# IndAlarmIf2.net
KiCad netlist of a schematic drawn in Altium Designer
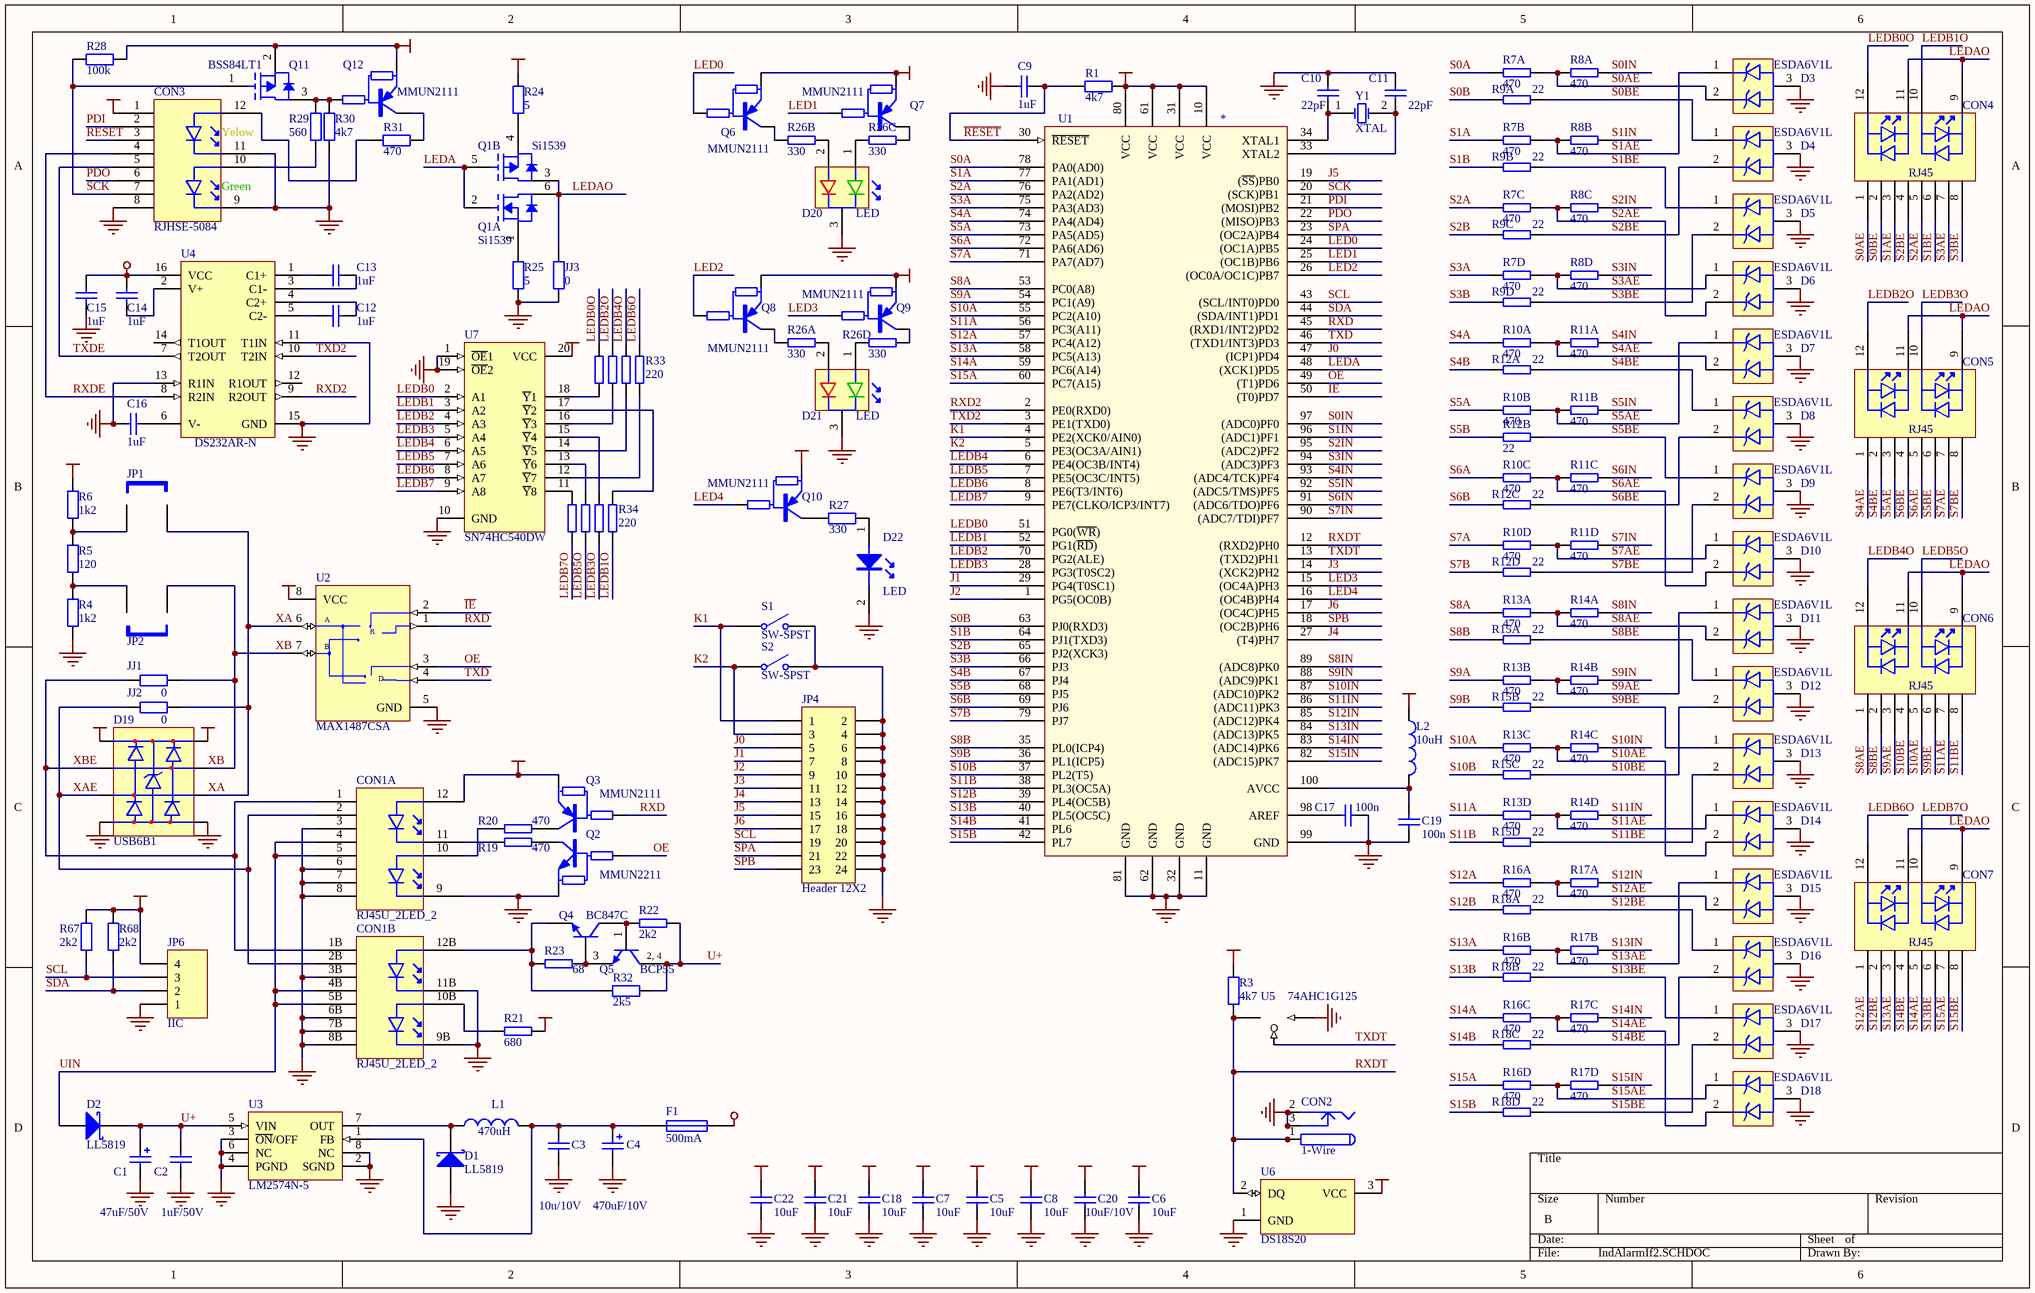
[diagram p0: IndAlarmIf2.SCHDOC]

(export (version "E")
  (design (tool "Eeschema 10.0.6"))
  (components
    (comp (ref "C1")
      (value "47uF/50V")
      (footprint "C8X11RM3.5")
      (description "Polarized Capacitor (Radial)")
      (fields (field (name "Comment") "Cap Pol1") (field (name "PUBLISHER") "Altium Limited"))
      (libsource (lib "Miscellaneous Devices") (part "Cap Pol1"))
    )
    (comp (ref "C2")
      (value "1uF/50V")
      (footprint "CC3225-1210")
      (description "Capacitor (Semiconductor SIM Model)")
      (fields (field (name "Comment") "Cap Semi") (field (name "PUBLISHER") "Altium Limited"))
      (libsource (lib "Miscellaneous Devices") (part "Cap Semi"))
    )
    (comp (ref "C3")
      (value "10u/10V")
      (footprint "CC3225-1210")
      (description "Capacitor (Semiconductor SIM Model)")
      (fields (field (name "Comment") "Cap Semi") (field (name "PUBLISHER") "Altium Limited"))
      (libsource (lib "Miscellaneous Devices") (part "Cap Semi"))
    )
    (comp (ref "C4")
      (value "470uF/10V")
      (footprint "C8X11RM3.5")
      (description "Polarized Capacitor (Radial)")
      (fields (field (name "Comment") "Cap Pol1") (field (name "PUBLISHER") "Altium Limited"))
      (libsource (lib "Miscellaneous Devices") (part "Cap Pol1"))
    )
    (comp (ref "C5")
      (value "10uF")
      (footprint "CC3216-1206")
      (description "Capacitor (Semiconductor SIM Model)")
      (fields (field (name "Comment") "Cap Semi") (field (name "PUBLISHER") "Altium Limited"))
      (libsource (lib "Miscellaneous Devices") (part "Cap Semi"))
    )
    (comp (ref "C6")
      (value "10uF")
      (footprint "CC3216-1206")
      (description "Capacitor (Semiconductor SIM Model)")
      (fields (field (name "Comment") "Cap Semi") (field (name "PUBLISHER") "Altium Limited"))
      (libsource (lib "Miscellaneous Devices") (part "Cap Semi"))
    )
    (comp (ref "C7")
      (value "10uF")
      (footprint "CC3216-1206")
      (description "Capacitor (Semiconductor SIM Model)")
      (fields (field (name "Comment") "Cap Semi") (field (name "PUBLISHER") "Altium Limited"))
      (libsource (lib "Miscellaneous Devices") (part "Cap Semi"))
    )
    (comp (ref "C8")
      (value "10uF")
      (footprint "CC3225-1210")
      (description "Capacitor (Semiconductor SIM Model)")
      (fields (field (name "Comment") "Cap Semi") (field (name "PUBLISHER") "Altium Limited"))
      (libsource (lib "Miscellaneous Devices") (part "Cap Semi"))
    )
    (comp (ref "C9")
      (value "1uF")
      (footprint "CC2012-0805")
      (description "Capacitor (Semiconductor SIM Model)")
      (fields (field (name "Comment") "Cap Semi") (field (name "PUBLISHER") "Altium Limited"))
      (libsource (lib "Miscellaneous Devices") (part "Cap Semi"))
    )
    (comp (ref "C10")
      (value "22pF")
      (footprint "CC2012-0805")
      (description "Capacitor (Semiconductor SIM Model)")
      (fields (field (name "Comment") "Cap Semi") (field (name "PUBLISHER") "Altium Limited"))
      (libsource (lib "Miscellaneous Devices") (part "Cap Semi"))
    )
    (comp (ref "C11")
      (value "22pF")
      (footprint "CC2012-0805")
      (description "Capacitor (Semiconductor SIM Model)")
      (fields (field (name "Comment") "Cap Semi") (field (name "PUBLISHER") "Altium Limited"))
      (libsource (lib "Miscellaneous Devices") (part "Cap Semi"))
    )
    (comp (ref "C12")
      (value "1uF")
      (footprint "CC2012-0805")
      (description "Capacitor (Semiconductor SIM Model)")
      (fields (field (name "Comment") "Cap Semi") (field (name "PUBLISHER") "Altium Limited"))
      (libsource (lib "Miscellaneous Devices") (part "Cap Semi"))
    )
    (comp (ref "C13")
      (value "1uF")
      (footprint "CC2012-0805")
      (description "Capacitor (Semiconductor SIM Model)")
      (fields (field (name "Comment") "Cap Semi") (field (name "PUBLISHER") "Altium Limited"))
      (libsource (lib "Miscellaneous Devices") (part "Cap Semi"))
    )
    (comp (ref "C14")
      (value "1uF")
      (footprint "CC2012-0805")
      (description "Capacitor (Semiconductor SIM Model)")
      (fields (field (name "Comment") "Cap Semi") (field (name "PUBLISHER") "Altium Limited"))
      (libsource (lib "Miscellaneous Devices") (part "Cap Semi"))
    )
    (comp (ref "C15")
      (value "1uF")
      (footprint "CC3216-1206")
      (description "Capacitor (Semiconductor SIM Model)")
      (fields (field (name "Comment") "Cap Semi") (field (name "PUBLISHER") "Altium Limited"))
      (libsource (lib "Miscellaneous Devices") (part "Cap Semi"))
    )
    (comp (ref "C16")
      (value "1uF")
      (footprint "CC2012-0805")
      (description "Capacitor (Semiconductor SIM Model)")
      (fields (field (name "Comment") "Cap Semi") (field (name "PUBLISHER") "Altium Limited"))
      (libsource (lib "Miscellaneous Devices") (part "Cap Semi"))
    )
    (comp (ref "C17")
      (value "100n")
      (footprint "CC2012-0805")
      (description "Capacitor (Semiconductor SIM Model)")
      (fields (field (name "Comment") "Cap Semi") (field (name "PUBLISHER") "Altium Limited"))
      (libsource (lib "Miscellaneous Devices") (part "Cap Semi"))
    )
    (comp (ref "C18")
      (value "10uF")
      (footprint "CC3216-1206")
      (description "Capacitor (Semiconductor SIM Model)")
      (fields (field (name "Comment") "Cap Semi") (field (name "PUBLISHER") "Altium Limited"))
      (libsource (lib "Miscellaneous Devices") (part "Cap Semi"))
    )
    (comp (ref "C19")
      (value "100n")
      (footprint "CC3216-1206")
      (description "Capacitor (Semiconductor SIM Model)")
      (fields (field (name "Comment") "Cap Semi") (field (name "PUBLISHER") "Altium Limited"))
      (libsource (lib "Miscellaneous Devices") (part "Cap Semi"))
    )
    (comp (ref "C20")
      (value "10uF/10V")
      (footprint "CC3216-1206")
      (description "Capacitor (Semiconductor SIM Model)")
      (fields (field (name "Comment") "Cap Semi") (field (name "PUBLISHER") "Altium Limited"))
      (libsource (lib "Miscellaneous Devices") (part "Cap Semi"))
    )
    (comp (ref "C21")
      (value "10uF")
      (footprint "CC3216-1206")
      (description "Capacitor (Semiconductor SIM Model)")
      (fields (field (name "Comment") "Cap Semi") (field (name "PUBLISHER") "Altium Limited"))
      (libsource (lib "Miscellaneous Devices") (part "Cap Semi"))
    )
    (comp (ref "C22")
      (value "10uF")
      (footprint "CC3216-1206")
      (description "Capacitor (Semiconductor SIM Model)")
      (fields (field (name "Comment") "Cap Semi") (field (name "PUBLISHER") "Altium Limited"))
      (libsource (lib "Miscellaneous Devices") (part "Cap Semi"))
    )
    (comp (ref "CON1")
      (value "RJ45U_2LED_2")
      (footprint "RJHS-508x-2")
      (libsource (lib "mySCHLIB") (part "RJ45U_2LED_2"))
    )
    (comp (ref "CON2")
      (value "1-Wire")
      (footprint "KLD-0202")
      (description "Low Voltage Power Supply Connector")
      (fields (field (name "PUBLISHER") "Altium Limited"))
      (libsource (lib "Miscellaneous Connectors") (part "PWR2.5"))
    )
    (comp (ref "CON3")
      (value "RJHSE-5084")
      (footprint "RJHS-508x")
      (libsource (lib "mySCHLIB") (part "RJ45U_2LED"))
    )
    (comp (ref "CON4")
      (value "RJ45")
      (footprint "RJHS-508x")
      (libsource (lib "mySCHLIB") (part "RJ45U_2LED_BI"))
    )
    (comp (ref "CON5")
      (value "RJ45")
      (footprint "RJHS-508x")
      (libsource (lib "mySCHLIB") (part "RJ45U_2LED_BI"))
    )
    (comp (ref "CON6")
      (value "RJ45")
      (footprint "RJHS-508x")
      (libsource (lib "mySCHLIB") (part "RJ45U_2LED_BI"))
    )
    (comp (ref "CON7")
      (value "RJ45")
      (footprint "RJHS-508x")
      (libsource (lib "mySCHLIB") (part "RJ45U_2LED_BI"))
    )
    (comp (ref "D1")
      (value "LL5819")
      (footprint "MELF")
      (description "Schottky Diode")
      (fields (field (name "PUBLISHER") "Altium Limited"))
      (libsource (lib "Miscellaneous Devices") (part "D Schottky"))
    )
    (comp (ref "D2")
      (value "LL5819")
      (footprint "MELF")
      (description "Schottky Diode")
      (fields (field (name "PUBLISHER") "Altium Limited"))
      (libsource (lib "Miscellaneous Devices") (part "D Schottky"))
    )
    (comp (ref "D3")
      (value "ESDA6V1L")
      (footprint "SO-G3/C2.5")
      (description "DUAL TRANSIL ARRAY\r\nFOR ESD PROTECTION")
      (libsource (lib "mySCHLIB") (part "ESDA6V1L"))
    )
    (comp (ref "D4")
      (value "ESDA6V1L")
      (footprint "SO-G3/C2.5")
      (description "DUAL TRANSIL ARRAY\r\nFOR ESD PROTECTION")
      (libsource (lib "mySCHLIB") (part "ESDA6V1L"))
    )
    (comp (ref "D5")
      (value "ESDA6V1L")
      (footprint "SO-G3/C2.5")
      (description "DUAL TRANSIL ARRAY\r\nFOR ESD PROTECTION")
      (libsource (lib "mySCHLIB") (part "ESDA6V1L"))
    )
    (comp (ref "D6")
      (value "ESDA6V1L")
      (footprint "SO-G3/C2.5")
      (description "DUAL TRANSIL ARRAY\r\nFOR ESD PROTECTION")
      (libsource (lib "mySCHLIB") (part "ESDA6V1L"))
    )
    (comp (ref "D7")
      (value "ESDA6V1L")
      (footprint "SO-G3/C2.5")
      (description "DUAL TRANSIL ARRAY\r\nFOR ESD PROTECTION")
      (libsource (lib "mySCHLIB") (part "ESDA6V1L"))
    )
    (comp (ref "D8")
      (value "ESDA6V1L")
      (footprint "SO-G3/C2.5")
      (description "DUAL TRANSIL ARRAY\r\nFOR ESD PROTECTION")
      (libsource (lib "mySCHLIB") (part "ESDA6V1L"))
    )
    (comp (ref "D9")
      (value "ESDA6V1L")
      (footprint "SO-G3/C2.5")
      (description "DUAL TRANSIL ARRAY\r\nFOR ESD PROTECTION")
      (libsource (lib "mySCHLIB") (part "ESDA6V1L"))
    )
    (comp (ref "D10")
      (value "ESDA6V1L")
      (footprint "SO-G3/C2.5")
      (description "DUAL TRANSIL ARRAY\r\nFOR ESD PROTECTION")
      (libsource (lib "mySCHLIB") (part "ESDA6V1L"))
    )
    (comp (ref "D11")
      (value "ESDA6V1L")
      (footprint "SO-G3/C2.5")
      (description "DUAL TRANSIL ARRAY\r\nFOR ESD PROTECTION")
      (libsource (lib "mySCHLIB") (part "ESDA6V1L"))
    )
    (comp (ref "D12")
      (value "ESDA6V1L")
      (footprint "SO-G3/C2.5")
      (description "DUAL TRANSIL ARRAY\r\nFOR ESD PROTECTION")
      (libsource (lib "mySCHLIB") (part "ESDA6V1L"))
    )
    (comp (ref "D13")
      (value "ESDA6V1L")
      (footprint "SO-G3/C2.5")
      (description "DUAL TRANSIL ARRAY\r\nFOR ESD PROTECTION")
      (libsource (lib "mySCHLIB") (part "ESDA6V1L"))
    )
    (comp (ref "D14")
      (value "ESDA6V1L")
      (footprint "SO-G3/C2.5")
      (description "DUAL TRANSIL ARRAY\r\nFOR ESD PROTECTION")
      (libsource (lib "mySCHLIB") (part "ESDA6V1L"))
    )
    (comp (ref "D15")
      (value "ESDA6V1L")
      (footprint "SO-G3/C2.5")
      (description "DUAL TRANSIL ARRAY\r\nFOR ESD PROTECTION")
      (libsource (lib "mySCHLIB") (part "ESDA6V1L"))
    )
    (comp (ref "D16")
      (value "ESDA6V1L")
      (footprint "SO-G3/C2.5")
      (description "DUAL TRANSIL ARRAY\r\nFOR ESD PROTECTION")
      (libsource (lib "mySCHLIB") (part "ESDA6V1L"))
    )
    (comp (ref "D17")
      (value "ESDA6V1L")
      (footprint "SO-G3/C2.5")
      (description "DUAL TRANSIL ARRAY\r\nFOR ESD PROTECTION")
      (libsource (lib "mySCHLIB") (part "ESDA6V1L"))
    )
    (comp (ref "D18")
      (value "ESDA6V1L")
      (footprint "SO-G3/C2.5")
      (description "DUAL TRANSIL ARRAY\r\nFOR ESD PROTECTION")
      (libsource (lib "mySCHLIB") (part "ESDA6V1L"))
    )
    (comp (ref "D19") (value "USB6B1") (footprint "NSO8") (libsource (lib "mySCHLIB") (part "USB6B1")))
    (comp (ref "D20") (value "LED") (footprint "LED3mm - 2") (libsource (lib "mySCHLIB") (part "2LED_A")))
    (comp (ref "D21") (value "LED") (footprint "LED3mm - 2") (libsource (lib "mySCHLIB") (part "2LED_A")))
    (comp (ref "D22") (value "LED") (footprint "myLIB:LED3mm") (libsource (lib "mySCHLIB") (part "LED12")))
    (comp (ref "F1")
      (value "500mA")
      (footprint "minifuse")
      (description "Fuse")
      (fields (field (name "PUBLISHER") "Altium Limited"))
      (libsource (lib "Miscellaneous Devices") (part "Fuse 1"))
    )
    (comp (ref "JJ1")
      (value "0")
      (footprint "CR2012-0805")
      (description "Semiconductor Resistor")
      (fields (field (name "PUBLISHER") "Altium Limited"))
      (libsource (lib "") (part "Res Semi_1"))
    )
    (comp (ref "JJ2")
      (value "0")
      (footprint "CR2012-0805")
      (description "Semiconductor Resistor")
      (fields (field (name "PUBLISHER") "Altium Limited"))
      (libsource (lib "") (part "Res Semi_1"))
    )
    (comp (ref "JJ3")
      (value "0")
      (footprint "CR2012-0805")
      (description "Semiconductor Resistor")
      (fields (field (name "PUBLISHER") "Altium Limited"))
      (libsource (lib "Miscellaneous Devices") (part "Res Semi"))
    )
    (comp (ref "JP1")
      (value "Jumper")
      (footprint "JP")
      (description "Jumper Wire")
      (fields (field (name "PUBLISHER") "Altium Limited"))
      (libsource (lib "Miscellaneous Devices") (part "Jumper"))
    )
    (comp (ref "JP2")
      (value "Jumper")
      (footprint "JP")
      (description "Jumper Wire")
      (fields (field (name "PUBLISHER") "Altium Limited"))
      (libsource (lib "Miscellaneous Devices") (part "Jumper"))
    )
    (comp (ref "JP4")
      (value "Header 12X2")
      (footprint "HDR2X12")
      (description "Header, 12-Pin, Dual row")
      (fields (field (name "PUBLISHER") "Altium Limited"))
      (libsource (lib "Miscellaneous Connectors") (part "Header 12X2"))
    )
    (comp (ref "JP6")
      (value "IIC")
      (footprint "HDR1X4")
      (description "Header, 4-Pin")
      (fields (field (name "PUBLISHER") "Altium Limited"))
      (libsource (lib "Miscellaneous Connectors") (part "Header 4"))
    )
    (comp (ref "L1")
      (value "470uH")
      (footprint "SSL1306T - NPI27H")
      (description "Inductor")
      (fields (field (name "PUBLISHER") "Altium Limited"))
      (libsource (lib "Miscellaneous Devices") (part "Inductor"))
    )
    (comp (ref "L2")
      (value "10uH")
      (footprint "CR3225-1210")
      (description "Inductor")
      (fields (field (name "PUBLISHER") "Altium Limited"))
      (libsource (lib "Miscellaneous Devices") (part "Inductor"))
    )
    (comp (ref "Q1") (value "Si1539") (footprint "SOT363") (libsource (lib "mySCHLIB") (part "Si1539")))
    (comp (ref "Q2")
      (value "MMUN2211")
      (footprint "SOT-23")
      (description "NPN Transistor")
      (libsource (lib "mySCHLIB") (part "NPNR1"))
    )
    (comp (ref "Q3")
      (value "MMUN2111")
      (footprint "SOT-23")
      (description "NPN Transistor")
      (libsource (lib "") (part "PNPR1_1"))
    )
    (comp (ref "Q4")
      (value "BC847C")
      (footprint "318-08")
      (description "General Purpose Transistor NPN Silicon")
      (fields (field (name "PUBLISHER") "Altium Limited"))
      (libsource (lib "Motorola Discrete BJT") (part "BC847ALT1"))
    )
    (comp (ref "Q5")
      (value "BCP55")
      (footprint "SOT223")
      (description "NPN Medium Power Transistor")
      (fields (field (name "PUBLISHER") "Altium Limited"))
      (libsource (lib "Philips Discrete BJT - Medium Power") (part "BCP55"))
    )
    (comp (ref "Q6")
      (value "MMUN2111")
      (footprint "SOT-23")
      (description "NPN Transistor")
      (libsource (lib "mySCHLIB") (part "PNPR1"))
    )
    (comp (ref "Q7")
      (value "MMUN2111")
      (footprint "SOT-23")
      (description "NPN Transistor")
      (libsource (lib "mySCHLIB") (part "PNPR1"))
    )
    (comp (ref "Q8")
      (value "MMUN2111")
      (footprint "SOT-23")
      (description "NPN Transistor")
      (libsource (lib "mySCHLIB") (part "PNPR1"))
    )
    (comp (ref "Q9")
      (value "MMUN2111")
      (footprint "SOT-23")
      (description "NPN Transistor")
      (libsource (lib "mySCHLIB") (part "PNPR1"))
    )
    (comp (ref "Q10")
      (value "MMUN2111")
      (footprint "SOT-23")
      (description "NPN Transistor")
      (libsource (lib "mySCHLIB") (part "PNPR1"))
    )
    (comp (ref "Q11") (value "BSS84LT1") (footprint "SOT23") (libsource (lib "mySCHLIB") (part "BSS84LT1")))
    (comp (ref "Q12")
      (value "MMUN2111")
      (footprint "SOT-23")
      (description "NPN Transistor")
      (libsource (lib "mySCHLIB") (part "PNPR1"))
    )
    (comp (ref "R1")
      (value "4k7")
      (footprint "CR2012-0805")
      (description "Semiconductor Resistor")
      (fields (field (name "Comment") "Res Semi") (field (name "PUBLISHER") "Altium Limited"))
      (libsource (lib "") (part "Res Semi_1"))
    )
    (comp (ref "R3")
      (value "4k7")
      (footprint "CR2012-0805")
      (description "Semiconductor Resistor")
      (fields (field (name "Comment") "Res Semi") (field (name "PUBLISHER") "Altium Limited"))
      (libsource (lib "Miscellaneous Devices") (part "Res Semi"))
    )
    (comp (ref "R4")
      (value "1k2")
      (footprint "CR2012-0805")
      (description "Semiconductor Resistor")
      (fields (field (name "Comment") "Res Semi") (field (name "PUBLISHER") "Altium Limited"))
      (libsource (lib "Miscellaneous Devices") (part "Res Semi"))
    )
    (comp (ref "R5")
      (value "120")
      (footprint "CR5025-2010")
      (description "Semiconductor Resistor")
      (fields (field (name "Comment") "Res Semi") (field (name "PUBLISHER") "Altium Limited"))
      (libsource (lib "Miscellaneous Devices") (part "Res Semi"))
    )
    (comp (ref "R6")
      (value "1k2")
      (footprint "CR2012-0805")
      (description "Semiconductor Resistor")
      (fields (field (name "Comment") "Res Semi") (field (name "PUBLISHER") "Altium Limited"))
      (libsource (lib "") (part "Res Semi_3"))
    )
    (comp (ref "R7") (value "470") (footprint "YC164") (libsource (lib "mySCHLIB") (part "RES4_1")))
    (comp (ref "R8") (value "470") (footprint "YC164") (libsource (lib "mySCHLIB") (part "RES4_1")))
    (comp (ref "R9") (value "22") (footprint "YC164") (libsource (lib "mySCHLIB") (part "RES4_1")))
    (comp (ref "R10") (value "470") (footprint "YC164") (libsource (lib "mySCHLIB") (part "RES4_1")))
    (comp (ref "R11") (value "470") (footprint "YC164") (libsource (lib "mySCHLIB") (part "RES4_1")))
    (comp (ref "R12") (value "22") (footprint "YC164") (libsource (lib "mySCHLIB") (part "RES4_1")))
    (comp (ref "R13") (value "470") (footprint "YC164") (libsource (lib "mySCHLIB") (part "RES4_1")))
    (comp (ref "R14") (value "470") (footprint "YC164") (libsource (lib "mySCHLIB") (part "RES4_1")))
    (comp (ref "R15") (value "22") (footprint "YC164") (libsource (lib "mySCHLIB") (part "RES4_1")))
    (comp (ref "R16") (value "470") (footprint "YC164") (libsource (lib "mySCHLIB") (part "RES4_1")))
    (comp (ref "R17") (value "470") (footprint "YC164") (libsource (lib "mySCHLIB") (part "RES4_1")))
    (comp (ref "R18") (value "22") (footprint "YC164") (libsource (lib "mySCHLIB") (part "RES4_1")))
    (comp (ref "R19") (value "470") (footprint "CR2012-0805") (libsource (lib "mySCHLIB") (part "RES2")))
    (comp (ref "R20") (value "470") (footprint "CR2012-0805") (libsource (lib "mySCHLIB") (part "RES2")))
    (comp (ref "R21") (value "680") (footprint "CR2012-0805") (libsource (lib "mySCHLIB") (part "RES2")))
    (comp (ref "R22") (value "2k2") (footprint "CR2012-0805") (libsource (lib "mySCHLIB") (part "RES2")))
    (comp (ref "R23") (value "68") (footprint "CR2012-0805") (libsource (lib "mySCHLIB") (part "RES2")))
    (comp (ref "R24")
      (value "5")
      (footprint "CR5025-2010")
      (description "Semiconductor Resistor")
      (fields (field (name "Comment") "Res Semi") (field (name "PUBLISHER") "Altium Limited"))
      (libsource (lib "Miscellaneous Devices") (part "Res Semi"))
    )
    (comp (ref "R25")
      (value "5")
      (footprint "CR5025-2010")
      (description "Semiconductor Resistor")
      (fields (field (name "Comment") "Res Semi") (field (name "PUBLISHER") "Altium Limited"))
      (libsource (lib "Miscellaneous Devices") (part "Res Semi"))
    )
    (comp (ref "R26") (value "330") (footprint "YC164") (libsource (lib "mySCHLIB") (part "RES4_1")))
    (comp (ref "R27")
      (value "330")
      (footprint "CR2012-0805")
      (description "Semiconductor Resistor")
      (fields (field (name "Comment") "Res Semi") (field (name "PUBLISHER") "Altium Limited"))
      (libsource (lib "") (part "Res Semi_2"))
    )
    (comp (ref "R28")
      (value "100k")
      (footprint "CR2012-0805")
      (description "Semiconductor Resistor")
      (fields (field (name "Comment") "Res Semi") (field (name "PUBLISHER") "Altium Limited"))
      (libsource (lib "") (part "Res Semi_1"))
    )
    (comp (ref "R29")
      (value "560")
      (footprint "CR2012-0805")
      (description "Semiconductor Resistor")
      (fields (field (name "Comment") "Res Semi") (field (name "PUBLISHER") "Altium Limited"))
      (libsource (lib "Miscellaneous Devices") (part "Res Semi"))
    )
    (comp (ref "R30")
      (value "4k7")
      (footprint "CR2012-0805")
      (description "Semiconductor Resistor")
      (fields (field (name "Comment") "Res Semi") (field (name "PUBLISHER") "Altium Limited"))
      (libsource (lib "Miscellaneous Devices") (part "Res Semi"))
    )
    (comp (ref "R31")
      (value "470")
      (footprint "CR2012-0805")
      (description "Semiconductor Resistor")
      (fields (field (name "Comment") "Res Semi") (field (name "PUBLISHER") "Altium Limited"))
      (libsource (lib "") (part "Res Semi_1"))
    )
    (comp (ref "R32")
      (value "2k5")
      (footprint "CR5025-2010")
      (description "Semiconductor Resistor")
      (fields (field (name "Comment") "Res Semi") (field (name "PUBLISHER") "Altium Limited"))
      (libsource (lib "") (part "Res Semi_2"))
    )
    (comp (ref "R33") (value "220") (footprint "YC164") (libsource (lib "mySCHLIB") (part "RES4")))
    (comp (ref "R34") (value "220") (footprint "YC164") (libsource (lib "mySCHLIB") (part "RES4")))
    (comp (ref "R67")
      (value "2k2")
      (footprint "CR2012-0805")
      (description "Semiconductor Resistor")
      (fields (field (name "Comment") "Res Semi") (field (name "PUBLISHER") "Altium Limited"))
      (libsource (lib "Miscellaneous Devices") (part "Res Semi"))
    )
    (comp (ref "R68")
      (value "2k2")
      (footprint "CR2012-0805")
      (description "Semiconductor Resistor")
      (fields (field (name "Comment") "Res Semi") (field (name "PUBLISHER") "Altium Limited"))
      (libsource (lib "Miscellaneous Devices") (part "Res Semi"))
    )
    (comp (ref "S1")
      (value "SW-SPST")
      (footprint "AXIAL-0.6")
      (description "Single-Pole, Single-Throw Switch")
      (fields (field (name "PUBLISHER") "Altium Limited"))
      (libsource (lib "Miscellaneous Devices") (part "SW-SPST"))
    )
    (comp (ref "S2")
      (value "SW-SPST")
      (footprint "AXIAL-0.6")
      (description "Single-Pole, Single-Throw Switch")
      (fields (field (name "PUBLISHER") "Altium Limited"))
      (libsource (lib "Miscellaneous Devices") (part "SW-SPST"))
    )
    (comp (ref "U1")
      (value "*")
      (footprint "Altera ACEX 1K:TQFP100")
      (libsource (lib "mySCHLIB") (part "ATMEGA1280"))
    )
    (comp (ref "U2")
      (value "MAX1487CSA")
      (footprint "NSO8")
      (description "Low-Power, Slew-Rate-Limited RS-485/RS-422 Transceiver")
      (fields (field (name "PUBLISHER") "Altium Limited"))
      (libsource (lib "Maxim Communication Transceiver") (part "MAX1487CSA"))
    )
    (comp (ref "U3")
      (value "LM2574N-5")
      (footprint "626-05")
      (description "Easy Switcher 0.5A Step-Down Voltage Regulator")
      (fields (field (name "PUBLISHER") "Altium Limited"))
      (libsource (lib "ON Semi Power Mgt Voltage Regulator") (part "LM2574N-5"))
    )
    (comp (ref "U4")
      (value "DS232AR-N")
      (footprint "SOIC16N")
      (description "Dual RS-232 Transmitter/Receiver")
      (fields (field (name "PUBLISHER") "Altium Limited"))
      (libsource (lib "Dallas Communication Transceiver") (part "DS232AR-N"))
    )
    (comp (ref "U5")
      (value "74AHC1G125")
      (footprint "SOT353")
      (libsource (lib "mySCHLIB") (part "74AHC1G125"))
    )
    (comp (ref "U6")
      (value "DS18S20")
      (footprint "PR35")
      (description "1-Wire Digital Thermometer")
      (fields (field (name "PUBLISHER") "Altium Limited"))
      (libsource (lib "Dallas Sensor Temperature Sensor") (part "DS1820"))
    )
    (comp (ref "U7")
      (value "SN74HC540DW")
      (footprint "DW020")
      (description "Octal Buffer and Line Driver with 3-State Outputs")
      (fields (field (name "PUBLISHER") "Altium Limited"))
      (libsource (lib "TI Logic Buffer Line Driver") (part "SN74HC540DW"))
    )
    (comp (ref "Y1")
      (value "XTAL")
      (footprint "myLIB:HC49")
      (description "Crystal Oscillator")
      (fields (field (name "PUBLISHER") "Altium Limited"))
      (libsource (lib "Miscellaneous Devices") (part "XTAL"))
    )
  )
  (nets
    (net (code "1") (name "/J0") (class "Default")
      (node (ref "JP4") (pin "5") (pinfunction "5_5") (pintype "passive"))
      (node (ref "U1") (pin "47") (pinfunction "(ICP1)PD4_47") (pintype "passive"))
    )
    (net (code "2") (name "/J1") (class "Default")
      (node (ref "JP4") (pin "7") (pinfunction "7_7") (pintype "passive"))
      (node (ref "U1") (pin "29") (pinfunction "PG4(T0SC1)_29") (pintype "passive"))
    )
    (net (code "3") (name "/J2") (class "Default")
      (node (ref "JP4") (pin "9") (pinfunction "9_9") (pintype "passive"))
      (node (ref "U1") (pin "1") (pinfunction "PG5(OC0B)_1") (pintype "passive"))
    )
    (net (code "4") (name "/J3") (class "Default")
      (node (ref "JP4") (pin "11") (pinfunction "11_11") (pintype "passive"))
      (node (ref "U1") (pin "14") (pinfunction "(XCK2)PH2_14") (pintype "passive"))
    )
    (net (code "5") (name "/J4") (class "Default")
      (node (ref "JP4") (pin "13") (pinfunction "13_13") (pintype "passive"))
      (node (ref "U1") (pin "27") (pinfunction "(T4)PH7_27") (pintype "passive"))
    )
    (net (code "6") (name "/J5") (class "Default")
      (node (ref "JP4") (pin "15") (pinfunction "15_15") (pintype "passive"))
      (node (ref "U1") (pin "19") (pinfunction "(~{SS})PB0_19") (pintype "passive"))
    )
    (net (code "7") (name "/J6") (class "Default")
      (node (ref "JP4") (pin "17") (pinfunction "17_17") (pintype "passive"))
      (node (ref "U1") (pin "17") (pinfunction "(OC4C)PH5_17") (pintype "passive"))
    )
    (net (code "8") (name "/K1") (class "Default")
      (node (ref "JP4") (pin "1") (pinfunction "1_1") (pintype "passive"))
      (node (ref "S1") (pin "1") (pinfunction "COMMON_1") (pintype "passive"))
      (node (ref "U1") (pin "4") (pinfunction "PE2(XCK0/AIN0)_4") (pintype "passive"))
    )
    (net (code "9") (name "/K2") (class "Default")
      (node (ref "JP4") (pin "3") (pinfunction "3_3") (pintype "passive"))
      (node (ref "S2") (pin "1") (pinfunction "COMMON_1") (pintype "passive"))
      (node (ref "U1") (pin "5") (pinfunction "PE3(OC3A/AIN1)_5") (pintype "passive"))
    )
    (net (code "10") (name "/LED0") (class "Default")
      (node (ref "Q6") (pin "1") (pinfunction "B_1") (pintype "passive"))
      (node (ref "U1") (pin "24") (pinfunction "(OC1A)PB5_24") (pintype "passive"))
    )
    (net (code "11") (name "/LED1") (class "Default")
      (node (ref "Q7") (pin "1") (pinfunction "B_1") (pintype "passive"))
      (node (ref "U1") (pin "25") (pinfunction "(OC1B)PB6_25") (pintype "passive"))
    )
    (net (code "12") (name "/LED2") (class "Default")
      (node (ref "Q8") (pin "1") (pinfunction "B_1") (pintype "passive"))
      (node (ref "U1") (pin "26") (pinfunction "(OC0A/OC1C)PB7_26") (pintype "passive"))
    )
    (net (code "13") (name "/LED3") (class "Default")
      (node (ref "Q9") (pin "1") (pinfunction "B_1") (pintype "passive"))
      (node (ref "U1") (pin "15") (pinfunction "(OC4A)PH3_15") (pintype "passive"))
    )
    (net (code "14") (name "/LED4") (class "Default")
      (node (ref "Q10") (pin "1") (pinfunction "B_1") (pintype "passive"))
      (node (ref "U1") (pin "16") (pinfunction "(OC4B)PH4_16") (pintype "passive"))
    )
    (net (code "15") (name "/LEDA") (class "Default")
      (node (ref "Q1") (pin "2") (pinfunction "G1_2") (pintype "passive"))
      (node (ref "Q1") (pin "5") (pinfunction "G2_5") (pintype "passive"))
      (node (ref "U1") (pin "48") (pinfunction "(XCK1)PD5_48") (pintype "passive"))
    )
    (net (code "16") (name "/LEDAO") (class "Default")
      (node (ref "CON4") (pin "11") (pinfunction "11_11") (pintype "passive"))
      (node (ref "CON4") (pin "9") (pinfunction "9_9") (pintype "passive"))
      (node (ref "CON5") (pin "11") (pinfunction "11_11") (pintype "passive"))
      (node (ref "CON5") (pin "9") (pinfunction "9_9") (pintype "passive"))
      (node (ref "CON6") (pin "11") (pinfunction "11_11") (pintype "passive"))
      (node (ref "CON6") (pin "9") (pinfunction "9_9") (pintype "passive"))
      (node (ref "CON7") (pin "11") (pinfunction "11_11") (pintype "passive"))
      (node (ref "CON7") (pin "9") (pinfunction "9_9") (pintype "passive"))
      (node (ref "JJ3") (pin "2") (pinfunction "2_2") (pintype "passive"))
      (node (ref "Q1") (pin "3") (pinfunction "D2_3") (pintype "passive"))
      (node (ref "Q1") (pin "6") (pinfunction "D1_6") (pintype "passive"))
    )
    (net (code "17") (name "/LEDB0") (class "Default")
      (node (ref "U1") (pin "51") (pinfunction "PG0(~{WR})_51") (pintype "passive"))
      (node (ref "U7") (pin "2") (pinfunction "A1_2") (pintype "input"))
    )
    (net (code "18") (name "/LEDB0O") (class "Default")
      (node (ref "CON4") (pin "12") (pinfunction "12_12") (pintype "passive"))
      (node (ref "R33") (pin "8") (pinfunction "6_8") (pintype "passive"))
    )
    (net (code "19") (name "/LEDB1") (class "Default")
      (node (ref "U1") (pin "52") (pinfunction "PG1(~{RD})_52") (pintype "passive"))
      (node (ref "U7") (pin "3") (pinfunction "A2_3") (pintype "input"))
    )
    (net (code "20") (name "/LEDB1O") (class "Default")
      (node (ref "CON4") (pin "10") (pinfunction "10_10") (pintype "passive"))
      (node (ref "R34") (pin "5") (pinfunction "5_5") (pintype "passive"))
    )
    (net (code "21") (name "/LEDB2") (class "Default")
      (node (ref "U1") (pin "70") (pinfunction "PG2(ALE)_70") (pintype "passive"))
      (node (ref "U7") (pin "4") (pinfunction "A3_4") (pintype "input"))
    )
    (net (code "22") (name "/LEDB2O") (class "Default")
      (node (ref "CON5") (pin "12") (pinfunction "12_12") (pintype "passive"))
      (node (ref "R33") (pin "7") (pinfunction "7_7") (pintype "passive"))
    )
    (net (code "23") (name "/LEDB3") (class "Default")
      (node (ref "U1") (pin "28") (pinfunction "PG3(T0SC2)_28") (pintype "passive"))
      (node (ref "U7") (pin "5") (pinfunction "A4_5") (pintype "input"))
    )
    (net (code "24") (name "/LEDB3O") (class "Default")
      (node (ref "CON5") (pin "10") (pinfunction "10_10") (pintype "passive"))
      (node (ref "R34") (pin "6") (pinfunction "6_6") (pintype "passive"))
    )
    (net (code "25") (name "/LEDB4") (class "Default")
      (node (ref "U1") (pin "6") (pinfunction "PE4(OC3B/INT4)_6") (pintype "passive"))
      (node (ref "U7") (pin "6") (pinfunction "A5_6") (pintype "input"))
    )
    (net (code "26") (name "/LEDB4O") (class "Default")
      (node (ref "CON6") (pin "12") (pinfunction "12_12") (pintype "passive"))
      (node (ref "R33") (pin "6") (pinfunction "6_6") (pintype "passive"))
    )
    (net (code "27") (name "/LEDB5") (class "Default")
      (node (ref "U1") (pin "7") (pinfunction "PE5(OC3C/INT5)_7") (pintype "passive"))
      (node (ref "U7") (pin "7") (pinfunction "A6_7") (pintype "input"))
    )
    (net (code "28") (name "/LEDB5O") (class "Default")
      (node (ref "CON6") (pin "10") (pinfunction "10_10") (pintype "passive"))
      (node (ref "R34") (pin "7") (pinfunction "7_7") (pintype "passive"))
    )
    (net (code "29") (name "/LEDB6") (class "Default")
      (node (ref "U1") (pin "8") (pinfunction "PE6(T3/INT6)_8") (pintype "passive"))
      (node (ref "U7") (pin "8") (pinfunction "A7_8") (pintype "input"))
    )
    (net (code "30") (name "/LEDB6O") (class "Default")
      (node (ref "CON7") (pin "12") (pinfunction "12_12") (pintype "passive"))
      (node (ref "R33") (pin "5") (pinfunction "5_5") (pintype "passive"))
    )
    (net (code "31") (name "/LEDB7") (class "Default")
      (node (ref "U1") (pin "9") (pinfunction "PE7(CLKO/ICP3/INT7)_9") (pintype "passive"))
      (node (ref "U7") (pin "9") (pinfunction "A8_9") (pintype "input"))
    )
    (net (code "32") (name "/LEDB7O") (class "Default")
      (node (ref "CON7") (pin "10") (pinfunction "10_10") (pintype "passive"))
      (node (ref "R34") (pin "8") (pinfunction "6_8") (pintype "passive"))
    )
    (net (code "33") (name "/OE") (class "Default")
      (node (ref "Q2") (pin "1") (pinfunction "B_1") (pintype "passive"))
      (node (ref "U1") (pin "49") (pinfunction "(T1)PD6_49") (pintype "passive"))
      (node (ref "U2") (pin "3") (pinfunction "DE_3") (pintype "input"))
    )
    (net (code "34") (name "/PDI") (class "Default")
      (node (ref "CON3") (pin "2") (pinfunction "2_2") (pintype "passive"))
      (node (ref "U1") (pin "21") (pinfunction "(MOSI)PB2_21") (pintype "passive"))
    )
    (net (code "35") (name "/PDO") (class "Default")
      (node (ref "CON3") (pin "6") (pinfunction "6_6") (pintype "passive"))
      (node (ref "U1") (pin "22") (pinfunction "(MISO)PB3_22") (pintype "passive"))
    )
    (net (code "36") (name "/RXD") (class "Default")
      (node (ref "Q3") (pin "1") (pinfunction "B_1") (pintype "passive"))
      (node (ref "U1") (pin "45") (pinfunction "(RXD1/INT2)PD2_45") (pintype "passive"))
      (node (ref "U2") (pin "1") (pinfunction "RO_1") (pintype "output"))
    )
    (net (code "37") (name "/RXD2") (class "Default")
      (node (ref "U1") (pin "2") (pinfunction "PE0(RXD0)_2") (pintype "passive"))
      (node (ref "U4") (pin "9") (pinfunction "R2OUT_9") (pintype "output"))
    )
    (net (code "38") (name "/RXDE") (class "Default")
      (node (ref "CON3") (pin "4") (pinfunction "4_4") (pintype "passive"))
      (node (ref "U4") (pin "8") (pinfunction "R2IN_8") (pintype "input"))
    )
    (net (code "39") (name "/RXDT") (class "Default")
      (node (ref "CON2") (pin "1") (pintype "power_in"))
      (node (ref "CON2") (pin "1A") (pintype "power_in"))
      (node (ref "CON2") (pin "1B") (pintype "power_in"))
      (node (ref "R3") (pin "1") (pinfunction "1_1") (pintype "passive"))
      (node (ref "U1") (pin "12") (pinfunction "(RXD2)PH0_12") (pintype "passive"))
      (node (ref "U5") (pin "4") (pinfunction "Y_4") (pintype "tri_state"))
      (node (ref "U6") (pin "2") (pinfunction "DQ_2") (pintype "bidirectional"))
    )
    (net (code "40") (name "/S0A") (class "Default")
      (node (ref "R7") (pin "8") (pinfunction "6_8") (pintype "passive"))
      (node (ref "U1") (pin "78") (pinfunction "PA0(AD0)_78") (pintype "passive"))
    )
    (net (code "41") (name "/S0AE") (class "Default")
      (node (ref "CON4") (pin "1") (pinfunction "1_1") (pintype "passive"))
      (node (ref "D3") (pin "2") (pinfunction "2_2") (pintype "passive"))
      (node (ref "R7") (pin "1") (pinfunction "1_1") (pintype "passive"))
      (node (ref "R8") (pin "8") (pinfunction "6_8") (pintype "passive"))
    )
    (net (code "42") (name "/S0B") (class "Default")
      (node (ref "R9") (pin "1") (pinfunction "1_1") (pintype "passive"))
      (node (ref "U1") (pin "63") (pinfunction "PJ0(RXD3)_63") (pintype "passive"))
    )
    (net (code "43") (name "/S0BE") (class "Default")
      (node (ref "CON4") (pin "2") (pinfunction "2_2") (pintype "passive"))
      (node (ref "D4") (pin "1") (pinfunction "1_1") (pintype "passive"))
      (node (ref "R9") (pin "8") (pinfunction "6_8") (pintype "passive"))
    )
    (net (code "44") (name "/S0IN") (class "Default")
      (node (ref "R8") (pin "1") (pinfunction "1_1") (pintype "passive"))
      (node (ref "U1") (pin "97") (pinfunction "(ADC0)PF0_97") (pintype "passive"))
    )
    (net (code "45") (name "/S1A") (class "Default")
      (node (ref "R7") (pin "7") (pinfunction "7_7") (pintype "passive"))
      (node (ref "U1") (pin "77") (pinfunction "PA1(AD1)_77") (pintype "passive"))
    )
    (net (code "46") (name "/S1AE") (class "Default")
      (node (ref "CON4") (pin "3") (pinfunction "3_3") (pintype "passive"))
      (node (ref "D3") (pin "1") (pinfunction "1_1") (pintype "passive"))
      (node (ref "R7") (pin "2") (pinfunction "2_2") (pintype "passive"))
      (node (ref "R8") (pin "7") (pinfunction "7_7") (pintype "passive"))
    )
    (net (code "47") (name "/S1B") (class "Default")
      (node (ref "R9") (pin "2") (pinfunction "2_2") (pintype "passive"))
      (node (ref "U1") (pin "64") (pinfunction "PJ1(TXD3)_64") (pintype "passive"))
    )
    (net (code "48") (name "/S1BE") (class "Default")
      (node (ref "CON4") (pin "6") (pinfunction "6_6") (pintype "passive"))
      (node (ref "D5") (pin "1") (pinfunction "1_1") (pintype "passive"))
      (node (ref "R9") (pin "7") (pinfunction "7_7") (pintype "passive"))
    )
    (net (code "49") (name "/S1IN") (class "Default")
      (node (ref "R8") (pin "2") (pinfunction "2_2") (pintype "passive"))
      (node (ref "U1") (pin "96") (pinfunction "(ADC1)PF1_96") (pintype "passive"))
    )
    (net (code "50") (name "/S2A") (class "Default")
      (node (ref "R7") (pin "6") (pinfunction "6_6") (pintype "passive"))
      (node (ref "U1") (pin "76") (pinfunction "PA2(AD2)_76") (pintype "passive"))
    )
    (net (code "51") (name "/S2AE") (class "Default")
      (node (ref "CON4") (pin "5") (pinfunction "5_5") (pintype "passive"))
      (node (ref "D6") (pin "2") (pinfunction "2_2") (pintype "passive"))
      (node (ref "R7") (pin "3") (pinfunction "3_3") (pintype "passive"))
      (node (ref "R8") (pin "6") (pinfunction "6_6") (pintype "passive"))
    )
    (net (code "52") (name "/S2B") (class "Default")
      (node (ref "R9") (pin "3") (pinfunction "3_3") (pintype "passive"))
      (node (ref "U1") (pin "65") (pinfunction "PJ2(XCK3)_65") (pintype "passive"))
    )
    (net (code "53") (name "/S2BE") (class "Default")
      (node (ref "CON4") (pin "4") (pinfunction "4_4") (pintype "passive"))
      (node (ref "D4") (pin "2") (pinfunction "2_2") (pintype "passive"))
      (node (ref "R9") (pin "6") (pinfunction "6_6") (pintype "passive"))
    )
    (net (code "54") (name "/S2IN") (class "Default")
      (node (ref "R8") (pin "3") (pinfunction "3_3") (pintype "passive"))
      (node (ref "U1") (pin "95") (pinfunction "(ADC2)PF2_95") (pintype "passive"))
    )
    (net (code "55") (name "/S3A") (class "Default")
      (node (ref "R7") (pin "5") (pinfunction "5_5") (pintype "passive"))
      (node (ref "U1") (pin "75") (pinfunction "PA3(AD3)_75") (pintype "passive"))
    )
    (net (code "56") (name "/S3AE") (class "Default")
      (node (ref "CON4") (pin "7") (pinfunction "7_7") (pintype "passive"))
      (node (ref "D6") (pin "1") (pinfunction "1_1") (pintype "passive"))
      (node (ref "R7") (pin "4") (pinfunction "4_4") (pintype "passive"))
      (node (ref "R8") (pin "5") (pinfunction "5_5") (pintype "passive"))
    )
    (net (code "57") (name "/S3B") (class "Default")
      (node (ref "R9") (pin "4") (pinfunction "4_4") (pintype "passive"))
      (node (ref "U1") (pin "66") (pinfunction "PJ3_66") (pintype "passive"))
    )
    (net (code "58") (name "/S3BE") (class "Default")
      (node (ref "CON4") (pin "8") (pinfunction "8_8") (pintype "passive"))
      (node (ref "D5") (pin "2") (pinfunction "2_2") (pintype "passive"))
      (node (ref "R9") (pin "5") (pinfunction "5_5") (pintype "passive"))
    )
    (net (code "59") (name "/S3IN") (class "Default")
      (node (ref "R8") (pin "4") (pinfunction "4_4") (pintype "passive"))
      (node (ref "U1") (pin "94") (pinfunction "(ADC3)PF3_94") (pintype "passive"))
    )
    (net (code "60") (name "/S4A") (class "Default")
      (node (ref "R10") (pin "8") (pinfunction "6_8") (pintype "passive"))
      (node (ref "U1") (pin "74") (pinfunction "PA4(AD4)_74") (pintype "passive"))
    )
    (net (code "61") (name "/S4AE") (class "Default")
      (node (ref "CON5") (pin "1") (pinfunction "1_1") (pintype "passive"))
      (node (ref "D7") (pin "2") (pinfunction "2_2") (pintype "passive"))
      (node (ref "R10") (pin "1") (pinfunction "1_1") (pintype "passive"))
      (node (ref "R11") (pin "8") (pinfunction "6_8") (pintype "passive"))
    )
    (net (code "62") (name "/S4B") (class "Default")
      (node (ref "R12") (pin "1") (pinfunction "1_1") (pintype "passive"))
      (node (ref "U1") (pin "67") (pinfunction "PJ4_67") (pintype "passive"))
    )
    (net (code "63") (name "/S4BE") (class "Default")
      (node (ref "CON5") (pin "2") (pinfunction "2_2") (pintype "passive"))
      (node (ref "D8") (pin "1") (pinfunction "1_1") (pintype "passive"))
      (node (ref "R12") (pin "8") (pinfunction "6_8") (pintype "passive"))
    )
    (net (code "64") (name "/S4IN") (class "Default")
      (node (ref "R11") (pin "1") (pinfunction "1_1") (pintype "passive"))
      (node (ref "U1") (pin "93") (pinfunction "(ADC4/TCK)PF4_93") (pintype "passive"))
    )
    (net (code "65") (name "/S5A") (class "Default")
      (node (ref "R10") (pin "7") (pinfunction "7_7") (pintype "passive"))
      (node (ref "U1") (pin "73") (pinfunction "PA5(AD5)_73") (pintype "passive"))
    )
    (net (code "66") (name "/S5AE") (class "Default")
      (node (ref "CON5") (pin "3") (pinfunction "3_3") (pintype "passive"))
      (node (ref "D7") (pin "1") (pinfunction "1_1") (pintype "passive"))
      (node (ref "R10") (pin "2") (pinfunction "2_2") (pintype "passive"))
      (node (ref "R11") (pin "7") (pinfunction "7_7") (pintype "passive"))
    )
    (net (code "67") (name "/S5B") (class "Default")
      (node (ref "R12") (pin "2") (pinfunction "2_2") (pintype "passive"))
      (node (ref "U1") (pin "68") (pinfunction "PJ5_68") (pintype "passive"))
    )
    (net (code "68") (name "/S5BE") (class "Default")
      (node (ref "CON5") (pin "6") (pinfunction "6_6") (pintype "passive"))
      (node (ref "D9") (pin "1") (pinfunction "1_1") (pintype "passive"))
      (node (ref "R12") (pin "7") (pinfunction "7_7") (pintype "passive"))
    )
    (net (code "69") (name "/S5IN") (class "Default")
      (node (ref "R11") (pin "2") (pinfunction "2_2") (pintype "passive"))
      (node (ref "U1") (pin "92") (pinfunction "(ADC5/TMS)PF5_92") (pintype "passive"))
    )
    (net (code "70") (name "/S6A") (class "Default")
      (node (ref "R10") (pin "6") (pinfunction "6_6") (pintype "passive"))
      (node (ref "U1") (pin "72") (pinfunction "PA6(AD6)_72") (pintype "passive"))
    )
    (net (code "71") (name "/S6AE") (class "Default")
      (node (ref "CON5") (pin "5") (pinfunction "5_5") (pintype "passive"))
      (node (ref "D10") (pin "2") (pinfunction "2_2") (pintype "passive"))
      (node (ref "R10") (pin "3") (pinfunction "3_3") (pintype "passive"))
      (node (ref "R11") (pin "6") (pinfunction "6_6") (pintype "passive"))
    )
    (net (code "72") (name "/S6B") (class "Default")
      (node (ref "R12") (pin "3") (pinfunction "3_3") (pintype "passive"))
      (node (ref "U1") (pin "69") (pinfunction "PJ6_69") (pintype "passive"))
    )
    (net (code "73") (name "/S6BE") (class "Default")
      (node (ref "CON5") (pin "4") (pinfunction "4_4") (pintype "passive"))
      (node (ref "D8") (pin "2") (pinfunction "2_2") (pintype "passive"))
      (node (ref "R12") (pin "6") (pinfunction "6_6") (pintype "passive"))
    )
    (net (code "74") (name "/S6IN") (class "Default")
      (node (ref "R11") (pin "3") (pinfunction "3_3") (pintype "passive"))
      (node (ref "U1") (pin "91") (pinfunction "(ADC6/TDO)PF6_91") (pintype "passive"))
    )
    (net (code "75") (name "/S7A") (class "Default")
      (node (ref "R10") (pin "5") (pinfunction "5_5") (pintype "passive"))
      (node (ref "U1") (pin "71") (pinfunction "PA7(AD7)_71") (pintype "passive"))
    )
    (net (code "76") (name "/S7AE") (class "Default")
      (node (ref "CON5") (pin "7") (pinfunction "7_7") (pintype "passive"))
      (node (ref "D10") (pin "1") (pinfunction "1_1") (pintype "passive"))
      (node (ref "R10") (pin "4") (pinfunction "4_4") (pintype "passive"))
      (node (ref "R11") (pin "5") (pinfunction "5_5") (pintype "passive"))
    )
    (net (code "77") (name "/S7B") (class "Default")
      (node (ref "R12") (pin "4") (pinfunction "4_4") (pintype "passive"))
      (node (ref "U1") (pin "79") (pinfunction "PJ7_79") (pintype "passive"))
    )
    (net (code "78") (name "/S7BE") (class "Default")
      (node (ref "CON5") (pin "8") (pinfunction "8_8") (pintype "passive"))
      (node (ref "D9") (pin "2") (pinfunction "2_2") (pintype "passive"))
      (node (ref "R12") (pin "5") (pinfunction "5_5") (pintype "passive"))
    )
    (net (code "79") (name "/S7IN") (class "Default")
      (node (ref "R11") (pin "4") (pinfunction "4_4") (pintype "passive"))
      (node (ref "U1") (pin "90") (pinfunction "(ADC7/TDI)PF7_90") (pintype "passive"))
    )
    (net (code "80") (name "/S8A") (class "Default")
      (node (ref "R13") (pin "8") (pinfunction "6_8") (pintype "passive"))
      (node (ref "U1") (pin "53") (pinfunction "PC0(A8)_53") (pintype "passive"))
    )
    (net (code "81") (name "/S8AE") (class "Default")
      (node (ref "CON6") (pin "1") (pinfunction "1_1") (pintype "passive"))
      (node (ref "D11") (pin "2") (pinfunction "2_2") (pintype "passive"))
      (node (ref "R13") (pin "1") (pinfunction "1_1") (pintype "passive"))
      (node (ref "R14") (pin "8") (pinfunction "6_8") (pintype "passive"))
    )
    (net (code "82") (name "/S8B") (class "Default")
      (node (ref "R15") (pin "1") (pinfunction "1_1") (pintype "passive"))
      (node (ref "U1") (pin "35") (pinfunction "PL0(ICP4)_35") (pintype "passive"))
    )
    (net (code "83") (name "/S8BE") (class "Default")
      (node (ref "CON6") (pin "2") (pinfunction "2_2") (pintype "passive"))
      (node (ref "D12") (pin "1") (pinfunction "1_1") (pintype "passive"))
      (node (ref "R15") (pin "8") (pinfunction "6_8") (pintype "passive"))
    )
    (net (code "84") (name "/S8IN") (class "Default")
      (node (ref "R14") (pin "1") (pinfunction "1_1") (pintype "passive"))
      (node (ref "U1") (pin "89") (pinfunction "(ADC8)PK0_89") (pintype "passive"))
    )
    (net (code "85") (name "/S9A") (class "Default")
      (node (ref "R13") (pin "7") (pinfunction "7_7") (pintype "passive"))
      (node (ref "U1") (pin "54") (pinfunction "PC1(A9)_54") (pintype "passive"))
    )
    (net (code "86") (name "/S9AE") (class "Default")
      (node (ref "CON6") (pin "3") (pinfunction "3_3") (pintype "passive"))
      (node (ref "D11") (pin "1") (pinfunction "1_1") (pintype "passive"))
      (node (ref "R13") (pin "2") (pinfunction "2_2") (pintype "passive"))
      (node (ref "R14") (pin "7") (pinfunction "7_7") (pintype "passive"))
    )
    (net (code "87") (name "/S9B") (class "Default")
      (node (ref "R15") (pin "2") (pinfunction "2_2") (pintype "passive"))
      (node (ref "U1") (pin "36") (pinfunction "PL1(ICP5)_36") (pintype "passive"))
    )
    (net (code "88") (name "/S9BE") (class "Default")
      (node (ref "CON6") (pin "6") (pinfunction "6_6") (pintype "passive"))
      (node (ref "D13") (pin "1") (pinfunction "1_1") (pintype "passive"))
      (node (ref "R15") (pin "7") (pinfunction "7_7") (pintype "passive"))
    )
    (net (code "89") (name "/S9IN") (class "Default")
      (node (ref "R14") (pin "2") (pinfunction "2_2") (pintype "passive"))
      (node (ref "U1") (pin "88") (pinfunction "(ADC9)PK1_88") (pintype "passive"))
    )
    (net (code "90") (name "/S10A") (class "Default")
      (node (ref "R13") (pin "6") (pinfunction "6_6") (pintype "passive"))
      (node (ref "U1") (pin "55") (pinfunction "PC2(A10)_55") (pintype "passive"))
    )
    (net (code "91") (name "/S10AE") (class "Default")
      (node (ref "CON6") (pin "5") (pinfunction "5_5") (pintype "passive"))
      (node (ref "D14") (pin "2") (pinfunction "2_2") (pintype "passive"))
      (node (ref "R13") (pin "3") (pinfunction "3_3") (pintype "passive"))
      (node (ref "R14") (pin "6") (pinfunction "6_6") (pintype "passive"))
    )
    (net (code "92") (name "/S10B") (class "Default")
      (node (ref "R15") (pin "3") (pinfunction "3_3") (pintype "passive"))
      (node (ref "U1") (pin "37") (pinfunction "PL2(T5)_37") (pintype "passive"))
    )
    (net (code "93") (name "/S10BE") (class "Default")
      (node (ref "CON6") (pin "4") (pinfunction "4_4") (pintype "passive"))
      (node (ref "D12") (pin "2") (pinfunction "2_2") (pintype "passive"))
      (node (ref "R15") (pin "6") (pinfunction "6_6") (pintype "passive"))
    )
    (net (code "94") (name "/S10IN") (class "Default")
      (node (ref "R14") (pin "3") (pinfunction "3_3") (pintype "passive"))
      (node (ref "U1") (pin "87") (pinfunction "(ADC10)PK2_87") (pintype "passive"))
    )
    (net (code "95") (name "/S11A") (class "Default")
      (node (ref "R13") (pin "5") (pinfunction "5_5") (pintype "passive"))
      (node (ref "U1") (pin "56") (pinfunction "PC3(A11)_56") (pintype "passive"))
    )
    (net (code "96") (name "/S11AE") (class "Default")
      (node (ref "CON6") (pin "7") (pinfunction "7_7") (pintype "passive"))
      (node (ref "D14") (pin "1") (pinfunction "1_1") (pintype "passive"))
      (node (ref "R13") (pin "4") (pinfunction "4_4") (pintype "passive"))
      (node (ref "R14") (pin "5") (pinfunction "5_5") (pintype "passive"))
    )
    (net (code "97") (name "/S11B") (class "Default")
      (node (ref "R15") (pin "4") (pinfunction "4_4") (pintype "passive"))
      (node (ref "U1") (pin "38") (pinfunction "PL3(OC5A)_38") (pintype "passive"))
    )
    (net (code "98") (name "/S11BE") (class "Default")
      (node (ref "CON6") (pin "8") (pinfunction "8_8") (pintype "passive"))
      (node (ref "D13") (pin "2") (pinfunction "2_2") (pintype "passive"))
      (node (ref "R15") (pin "5") (pinfunction "5_5") (pintype "passive"))
    )
    (net (code "99") (name "/S11IN") (class "Default")
      (node (ref "R14") (pin "4") (pinfunction "4_4") (pintype "passive"))
      (node (ref "U1") (pin "86") (pinfunction "(ADC11)PK3_86") (pintype "passive"))
    )
    (net (code "100") (name "/S12A") (class "Default")
      (node (ref "R16") (pin "8") (pinfunction "6_8") (pintype "passive"))
      (node (ref "U1") (pin "57") (pinfunction "PC4(A12)_57") (pintype "passive"))
    )
    (net (code "101") (name "/S12AE") (class "Default")
      (node (ref "CON7") (pin "1") (pinfunction "1_1") (pintype "passive"))
      (node (ref "D15") (pin "2") (pinfunction "2_2") (pintype "passive"))
      (node (ref "R16") (pin "1") (pinfunction "1_1") (pintype "passive"))
      (node (ref "R17") (pin "8") (pinfunction "6_8") (pintype "passive"))
    )
    (net (code "102") (name "/S12B") (class "Default")
      (node (ref "R18") (pin "1") (pinfunction "1_1") (pintype "passive"))
      (node (ref "U1") (pin "39") (pinfunction "PL4(OC5B)_39") (pintype "passive"))
    )
    (net (code "103") (name "/S12BE") (class "Default")
      (node (ref "CON7") (pin "2") (pinfunction "2_2") (pintype "passive"))
      (node (ref "D16") (pin "1") (pinfunction "1_1") (pintype "passive"))
      (node (ref "R18") (pin "8") (pinfunction "6_8") (pintype "passive"))
    )
    (net (code "104") (name "/S12IN") (class "Default")
      (node (ref "R17") (pin "1") (pinfunction "1_1") (pintype "passive"))
      (node (ref "U1") (pin "85") (pinfunction "(ADC12)PK4_85") (pintype "passive"))
    )
    (net (code "105") (name "/S13A") (class "Default")
      (node (ref "R16") (pin "7") (pinfunction "7_7") (pintype "passive"))
      (node (ref "U1") (pin "58") (pinfunction "PC5(A13)_58") (pintype "passive"))
    )
    (net (code "106") (name "/S13AE") (class "Default")
      (node (ref "CON7") (pin "3") (pinfunction "3_3") (pintype "passive"))
      (node (ref "D15") (pin "1") (pinfunction "1_1") (pintype "passive"))
      (node (ref "R16") (pin "2") (pinfunction "2_2") (pintype "passive"))
      (node (ref "R17") (pin "7") (pinfunction "7_7") (pintype "passive"))
    )
    (net (code "107") (name "/S13B") (class "Default")
      (node (ref "R18") (pin "2") (pinfunction "2_2") (pintype "passive"))
      (node (ref "U1") (pin "40") (pinfunction "PL5(OC5C)_40") (pintype "passive"))
    )
    (net (code "108") (name "/S13BE") (class "Default")
      (node (ref "CON7") (pin "6") (pinfunction "6_6") (pintype "passive"))
      (node (ref "D17") (pin "1") (pinfunction "1_1") (pintype "passive"))
      (node (ref "R18") (pin "7") (pinfunction "7_7") (pintype "passive"))
    )
    (net (code "109") (name "/S13IN") (class "Default")
      (node (ref "R17") (pin "2") (pinfunction "2_2") (pintype "passive"))
      (node (ref "U1") (pin "84") (pinfunction "(ADC13)PK5_84") (pintype "passive"))
    )
    (net (code "110") (name "/S14A") (class "Default")
      (node (ref "R16") (pin "6") (pinfunction "6_6") (pintype "passive"))
      (node (ref "U1") (pin "59") (pinfunction "PC6(A14)_59") (pintype "passive"))
    )
    (net (code "111") (name "/S14AE") (class "Default")
      (node (ref "CON7") (pin "5") (pinfunction "5_5") (pintype "passive"))
      (node (ref "D18") (pin "2") (pinfunction "2_2") (pintype "passive"))
      (node (ref "R16") (pin "3") (pinfunction "3_3") (pintype "passive"))
      (node (ref "R17") (pin "6") (pinfunction "6_6") (pintype "passive"))
    )
    (net (code "112") (name "/S14B") (class "Default")
      (node (ref "R18") (pin "3") (pinfunction "3_3") (pintype "passive"))
      (node (ref "U1") (pin "41") (pinfunction "PL6_41") (pintype "passive"))
    )
    (net (code "113") (name "/S14BE") (class "Default")
      (node (ref "CON7") (pin "4") (pinfunction "4_4") (pintype "passive"))
      (node (ref "D16") (pin "2") (pinfunction "2_2") (pintype "passive"))
      (node (ref "R18") (pin "6") (pinfunction "6_6") (pintype "passive"))
    )
    (net (code "114") (name "/S14IN") (class "Default")
      (node (ref "R17") (pin "3") (pinfunction "3_3") (pintype "passive"))
      (node (ref "U1") (pin "83") (pinfunction "(ADC14)PK6_83") (pintype "passive"))
    )
    (net (code "115") (name "/S15A") (class "Default")
      (node (ref "R16") (pin "5") (pinfunction "5_5") (pintype "passive"))
      (node (ref "U1") (pin "60") (pinfunction "PC7(A15)_60") (pintype "passive"))
    )
    (net (code "116") (name "/S15AE") (class "Default")
      (node (ref "CON7") (pin "7") (pinfunction "7_7") (pintype "passive"))
      (node (ref "D18") (pin "1") (pinfunction "1_1") (pintype "passive"))
      (node (ref "R16") (pin "4") (pinfunction "4_4") (pintype "passive"))
      (node (ref "R17") (pin "5") (pinfunction "5_5") (pintype "passive"))
    )
    (net (code "117") (name "/S15B") (class "Default")
      (node (ref "R18") (pin "4") (pinfunction "4_4") (pintype "passive"))
      (node (ref "U1") (pin "42") (pinfunction "PL7_42") (pintype "passive"))
    )
    (net (code "118") (name "/S15BE") (class "Default")
      (node (ref "CON7") (pin "8") (pinfunction "8_8") (pintype "passive"))
      (node (ref "D17") (pin "2") (pinfunction "2_2") (pintype "passive"))
      (node (ref "R18") (pin "5") (pinfunction "5_5") (pintype "passive"))
    )
    (net (code "119") (name "/S15IN") (class "Default")
      (node (ref "R17") (pin "4") (pinfunction "4_4") (pintype "passive"))
      (node (ref "U1") (pin "82") (pinfunction "(ADC15)PK7_82") (pintype "passive"))
    )
    (net (code "120") (name "/SCK") (class "Default")
      (node (ref "CON3") (pin "7") (pinfunction "7_7") (pintype "passive"))
      (node (ref "Q11") (pin "1") (pinfunction "G_1") (pintype "passive"))
      (node (ref "R28") (pin "1") (pinfunction "1_1") (pintype "passive"))
      (node (ref "U1") (pin "20") (pinfunction "(SCK)PB1_20") (pintype "passive"))
    )
    (net (code "121") (name "/SCL") (class "Default")
      (node (ref "JP4") (pin "19") (pinfunction "19_19") (pintype "passive"))
      (node (ref "JP6") (pin "3") (pinfunction "3_3") (pintype "passive"))
      (node (ref "R67") (pin "1") (pinfunction "1_1") (pintype "passive"))
      (node (ref "U1") (pin "43") (pinfunction "(SCL/INT0)PD0_43") (pintype "passive"))
    )
    (net (code "122") (name "/SDA") (class "Default")
      (node (ref "JP6") (pin "2") (pinfunction "2_2") (pintype "passive"))
      (node (ref "R68") (pin "1") (pinfunction "1_1") (pintype "passive"))
      (node (ref "U1") (pin "44") (pinfunction "(SDA/INT1)PD1_44") (pintype "passive"))
    )
    (net (code "123") (name "/SPA") (class "Default")
      (node (ref "JP4") (pin "21") (pinfunction "21_21") (pintype "passive"))
      (node (ref "U1") (pin "23") (pinfunction "(OC2A)PB4_23") (pintype "passive"))
    )
    (net (code "124") (name "/SPB") (class "Default")
      (node (ref "JP4") (pin "23") (pinfunction "23_23") (pintype "passive"))
      (node (ref "U1") (pin "18") (pinfunction "(OC2B)PH6_18") (pintype "passive"))
    )
    (net (code "125") (name "/TXD") (class "Default")
      (node (ref "U1") (pin "46") (pinfunction "(TXD1/INT3)PD3_46") (pintype "passive"))
      (node (ref "U2") (pin "4") (pinfunction "DI_4") (pintype "input"))
    )
    (net (code "126") (name "/TXD2") (class "Default")
      (node (ref "U1") (pin "3") (pinfunction "PE1(TXD0)_3") (pintype "passive"))
      (node (ref "U4") (pin "10") (pinfunction "T2IN_10") (pintype "input"))
    )
    (net (code "127") (name "/TXDE") (class "Default")
      (node (ref "CON3") (pin "5") (pinfunction "5_5") (pintype "passive"))
      (node (ref "U4") (pin "7") (pinfunction "T2OUT_7") (pintype "output"))
    )
    (net (code "128") (name "/TXDT") (class "Default")
      (node (ref "U1") (pin "13") (pinfunction "(TXD2)PH1_13") (pintype "passive"))
      (node (ref "U5") (pin "1") (pinfunction "~{OE}_1") (pintype "input"))
    )
    (net (code "129") (name "/U+") (class "Default")
      (node (ref "C1") (pin "1") (pinfunction "1_1") (pintype "passive"))
      (node (ref "C2") (pin "2") (pinfunction "2_2") (pintype "passive"))
      (node (ref "D2") (pin "2") (pinfunction "K_2") (pintype "passive"))
      (node (ref "Q5") (pin "2") (pinfunction "C_2") (pintype "passive"))
      (node (ref "Q5") (pin "4") (pinfunction "C_4") (pintype "passive"))
      (node (ref "R22") (pin "2") (pinfunction "2_2") (pintype "passive"))
      (node (ref "R32") (pin "1") (pinfunction "1_1") (pintype "passive"))
      (node (ref "U3") (pin "5") (pinfunction "VIN_5") (pintype "input"))
    )
    (net (code "130") (name "/UIN") (class "Default")
      (node (ref "CON1") (pin "4") (pinfunction "4_4") (pintype "passive"))
      (node (ref "CON1") (pin "4B") (pinfunction "4B_4B") (pintype "passive"))
      (node (ref "CON1") (pin "5") (pinfunction "5_5") (pintype "passive"))
      (node (ref "CON1") (pin "5B") (pinfunction "5B_5B") (pintype "passive"))
      (node (ref "D2") (pin "1") (pinfunction "A_1") (pintype "passive"))
    )
    (net (code "131") (name "/XA") (class "Default")
      (node (ref "D19") (pin "3") (pinfunction "I/O2_3") (pintype "passive"))
      (node (ref "JJ2") (pin "2") (pinfunction "2_2") (pintype "passive"))
      (node (ref "JP1") (pin "2") (pinfunction "2_2") (pintype "passive"))
      (node (ref "U2") (pin "6") (pinfunction "A_6") (pintype "bidirectional"))
    )
    (net (code "132") (name "/XAE") (class "Default")
      (node (ref "CON1") (pin "2") (pinfunction "2_2") (pintype "passive"))
      (node (ref "CON1") (pin "2B") (pinfunction "2B_2B") (pintype "passive"))
      (node (ref "D19") (pin "6") (pinfunction "I/O2_6") (pintype "passive"))
      (node (ref "JJ2") (pin "1") (pinfunction "1_1") (pintype "passive"))
    )
    (net (code "133") (name "/XB") (class "Default")
      (node (ref "D19") (pin "2") (pinfunction "I/O1_2") (pintype "passive"))
      (node (ref "JJ1") (pin "2") (pinfunction "2_2") (pintype "passive"))
      (node (ref "JP2") (pin "1") (pinfunction "1_1") (pintype "passive"))
      (node (ref "U2") (pin "7") (pinfunction "B_7") (pintype "bidirectional"))
    )
    (net (code "134") (name "/XBE") (class "Default")
      (node (ref "CON1") (pin "1") (pinfunction "1_1") (pintype "passive"))
      (node (ref "CON1") (pin "1B") (pinfunction "1B_1B") (pintype "passive"))
      (node (ref "D19") (pin "7") (pinfunction "I/O1_7") (pintype "passive"))
      (node (ref "JJ1") (pin "1") (pinfunction "1_1") (pintype "passive"))
    )
    (net (code "135") (name "/~{IE}") (class "Default")
      (node (ref "U1") (pin "50") (pinfunction "(T0)PD7_50") (pintype "passive"))
      (node (ref "U2") (pin "2") (pinfunction "~{RE}_2") (pintype "input"))
    )
    (net (code "136") (name "/~{RESET}") (class "Default")
      (node (ref "C9") (pin "1") (pinfunction "1_1") (pintype "passive"))
      (node (ref "CON3") (pin "3") (pinfunction "3_3") (pintype "passive"))
      (node (ref "R1") (pin "1") (pinfunction "1_1") (pintype "passive"))
      (node (ref "U1") (pin "30") (pinfunction "~{RESET}_30") (pintype "input"))
    )
    (net (code "137") (name "GND") (class "Default")
      (node (ref "C1") (pin "2") (pinfunction "2_2") (pintype "passive"))
      (node (ref "C10") (pin "2") (pinfunction "2_2") (pintype "passive"))
      (node (ref "C11") (pin "2") (pinfunction "2_2") (pintype "passive"))
      (node (ref "C15") (pin "2") (pinfunction "2_2") (pintype "passive"))
      (node (ref "C16") (pin "1") (pinfunction "1_1") (pintype "passive"))
      (node (ref "C17") (pin "1") (pinfunction "1_1") (pintype "passive"))
      (node (ref "C18") (pin "1") (pinfunction "1_1") (pintype "passive"))
      (node (ref "C19") (pin "1") (pinfunction "1_1") (pintype "passive"))
      (node (ref "C2") (pin "1") (pinfunction "1_1") (pintype "passive"))
      (node (ref "C20") (pin "1") (pinfunction "1_1") (pintype "passive"))
      (node (ref "C21") (pin "1") (pinfunction "1_1") (pintype "passive"))
      (node (ref "C22") (pin "1") (pinfunction "1_1") (pintype "passive"))
      (node (ref "C3") (pin "1") (pinfunction "1_1") (pintype "passive"))
      (node (ref "C4") (pin "2") (pinfunction "2_2") (pintype "passive"))
      (node (ref "C5") (pin "1") (pinfunction "1_1") (pintype "passive"))
      (node (ref "C6") (pin "1") (pinfunction "1_1") (pintype "passive"))
      (node (ref "C7") (pin "1") (pinfunction "1_1") (pintype "passive"))
      (node (ref "C8") (pin "1") (pinfunction "1_1") (pintype "passive"))
      (node (ref "C9") (pin "2") (pinfunction "2_2") (pintype "passive"))
      (node (ref "CON1") (pin "11B") (pinfunction "11B_11B") (pintype "passive"))
      (node (ref "CON1") (pin "3") (pinfunction "3_3") (pintype "passive"))
      (node (ref "CON1") (pin "3B") (pinfunction "3B_3B") (pintype "passive"))
      (node (ref "CON1") (pin "6") (pinfunction "6_6") (pintype "passive"))
      (node (ref "CON1") (pin "6B") (pinfunction "6B_6B") (pintype "passive"))
      (node (ref "CON1") (pin "7") (pinfunction "7_7") (pintype "passive"))
      (node (ref "CON1") (pin "7B") (pinfunction "7B_7B") (pintype "passive"))
      (node (ref "CON1") (pin "8") (pinfunction "8_8") (pintype "passive"))
      (node (ref "CON1") (pin "8B") (pinfunction "8B_8B") (pintype "passive"))
      (node (ref "CON1") (pin "9") (pinfunction "9_9") (pintype "passive"))
      (node (ref "CON1") (pin "9B") (pinfunction "9B_9B") (pintype "passive"))
      (node (ref "CON2") (pin "2") (pintype "power_in"))
      (node (ref "CON2") (pin "2A") (pintype "power_in"))
      (node (ref "CON2") (pin "2B") (pintype "power_in"))
      (node (ref "CON2") (pin "3") (pintype "power_in"))
      (node (ref "CON2") (pin "3A") (pintype "power_in"))
      (node (ref "CON2") (pin "3B") (pintype "power_in"))
      (node (ref "CON3") (pin "11") (pinfunction "11_11") (pintype "passive"))
      (node (ref "CON3") (pin "8") (pinfunction "8_8") (pintype "passive"))
      (node (ref "CON3") (pin "9") (pinfunction "9_9") (pintype "passive"))
      (node (ref "D1") (pin "1") (pinfunction "A_1") (pintype "passive"))
      (node (ref "D10") (pin "3") (pinfunction "3_3") (pintype "passive"))
      (node (ref "D11") (pin "3") (pinfunction "3_3") (pintype "passive"))
      (node (ref "D12") (pin "3") (pinfunction "3_3") (pintype "passive"))
      (node (ref "D13") (pin "3") (pinfunction "3_3") (pintype "passive"))
      (node (ref "D14") (pin "3") (pinfunction "3_3") (pintype "passive"))
      (node (ref "D15") (pin "3") (pinfunction "3_3") (pintype "passive"))
      (node (ref "D16") (pin "3") (pinfunction "3_3") (pintype "passive"))
      (node (ref "D17") (pin "3") (pinfunction "3_3") (pintype "passive"))
      (node (ref "D18") (pin "3") (pinfunction "3_3") (pintype "passive"))
      (node (ref "D19") (pin "4") (pinfunction "GND_4") (pintype "power_in"))
      (node (ref "D19") (pin "5") (pinfunction "GND_5") (pintype "power_in"))
      (node (ref "D20") (pin "3") (pinfunction "3_3") (pintype "passive"))
      (node (ref "D21") (pin "3") (pinfunction "3_3") (pintype "passive"))
      (node (ref "D22") (pin "2") (pinfunction "2_2") (pintype "passive"))
      (node (ref "D3") (pin "3") (pinfunction "3_3") (pintype "passive"))
      (node (ref "D4") (pin "3") (pinfunction "3_3") (pintype "passive"))
      (node (ref "D5") (pin "3") (pinfunction "3_3") (pintype "passive"))
      (node (ref "D6") (pin "3") (pinfunction "3_3") (pintype "passive"))
      (node (ref "D7") (pin "3") (pinfunction "3_3") (pintype "passive"))
      (node (ref "D8") (pin "3") (pinfunction "3_3") (pintype "passive"))
      (node (ref "D9") (pin "3") (pinfunction "3_3") (pintype "passive"))
      (node (ref "JJ3") (pin "1") (pinfunction "1_1") (pintype "passive"))
      (node (ref "JP4") (pin "10") (pinfunction "10_10") (pintype "passive"))
      (node (ref "JP4") (pin "12") (pinfunction "12_12") (pintype "passive"))
      (node (ref "JP4") (pin "14") (pinfunction "14_14") (pintype "passive"))
      (node (ref "JP4") (pin "16") (pinfunction "16_16") (pintype "passive"))
      (node (ref "JP4") (pin "18") (pinfunction "18_18") (pintype "passive"))
      (node (ref "JP4") (pin "2") (pinfunction "2_2") (pintype "passive"))
      (node (ref "JP4") (pin "20") (pinfunction "20_20") (pintype "passive"))
      (node (ref "JP4") (pin "22") (pinfunction "22_22") (pintype "passive"))
      (node (ref "JP4") (pin "24") (pinfunction "24_24") (pintype "passive"))
      (node (ref "JP4") (pin "4") (pinfunction "4_4") (pintype "passive"))
      (node (ref "JP4") (pin "6") (pinfunction "6_6") (pintype "passive"))
      (node (ref "JP4") (pin "8") (pinfunction "8_8") (pintype "passive"))
      (node (ref "JP6") (pin "1") (pinfunction "1_1") (pintype "passive"))
      (node (ref "Q2") (pin "2") (pinfunction "E_2") (pintype "passive"))
      (node (ref "R25") (pin "1") (pinfunction "1_1") (pintype "passive"))
      (node (ref "R30") (pin "1") (pinfunction "1_1") (pintype "passive"))
      (node (ref "R4") (pin "1") (pinfunction "1_1") (pintype "passive"))
      (node (ref "S1") (pin "2") (pinfunction "NO_2") (pintype "passive"))
      (node (ref "S2") (pin "2") (pinfunction "NO_2") (pintype "passive"))
      (node (ref "U1") (pin "11") (pinfunction "GND_11") (pintype "passive"))
      (node (ref "U1") (pin "32") (pinfunction "GND_32") (pintype "passive"))
      (node (ref "U1") (pin "62") (pinfunction "GND_62") (pintype "power_in"))
      (node (ref "U1") (pin "81") (pinfunction "GND_81") (pintype "power_in"))
      (node (ref "U1") (pin "99") (pinfunction "GND_99") (pintype "power_in"))
      (node (ref "U2") (pin "5") (pinfunction "GND_5") (pintype "power_in"))
      (node (ref "U3") (pin "2") (pinfunction "SGND_2") (pintype "power_in"))
      (node (ref "U3") (pin "3") (pinfunction "~{ON}/OFF_3") (pintype "passive"))
      (node (ref "U3") (pin "4") (pinfunction "PGND_4") (pintype "power_in"))
      (node (ref "U3") (pin "6") (pinfunction "NC_6") (pintype "passive"))
      (node (ref "U3") (pin "8") (pinfunction "NC_8") (pintype "passive"))
      (node (ref "U4") (pin "11") (pinfunction "T1IN_11") (pintype "input"))
      (node (ref "U4") (pin "13") (pinfunction "R1IN_13") (pintype "input"))
      (node (ref "U4") (pin "15") (pinfunction "GND_15") (pintype "power_in"))
      (node (ref "U5") (pin "2") (pinfunction "A_2") (pintype "input"))
      (node (ref "U5") (pin "3") (pinfunction "GND_3") (pintype "power_in"))
      (node (ref "U6") (pin "1") (pinfunction "GND_1") (pintype "power_in"))
      (node (ref "U7") (pin "1") (pinfunction "~{OE}1_1") (pintype "input"))
      (node (ref "U7") (pin "10") (pinfunction "GND_10") (pintype "power_in"))
      (node (ref "U7") (pin "19") (pinfunction "~{OE}2_19") (pintype "input"))
    )
    (net (code "138") (name "Net-(CON1-Pad10)") (class "Default")
      (node (ref "CON1") (pin "10") (pinfunction "10_10") (pintype "passive"))
      (node (ref "R20") (pin "1") (pinfunction "1_1") (pintype "passive"))
    )
    (net (code "139") (name "Net-(CON1-Pad10B)") (class "Default")
      (node (ref "CON1") (pin "10B") (pinfunction "10B_10B") (pintype "passive"))
      (node (ref "R21") (pin "1") (pinfunction "1_1") (pintype "passive"))
    )
    (net (code "140") (name "Net-(CON1-Pad11)") (class "Default")
      (node (ref "CON1") (pin "11") (pinfunction "11_11") (pintype "passive"))
      (node (ref "R19") (pin "1") (pinfunction "1_1") (pintype "passive"))
    )
    (net (code "141") (name "Net-(CON3-Pad10)") (class "Default")
      (node (ref "CON3") (pin "10") (pinfunction "10_10") (pintype "passive"))
      (node (ref "R29") (pin "1") (pinfunction "1_1") (pintype "passive"))
    )
    (net (code "142") (name "Net-(CON3-Pad12)") (class "Default")
      (node (ref "CON3") (pin "12") (pinfunction "12_12") (pintype "passive"))
      (node (ref "R31") (pin "1") (pinfunction "1_1") (pintype "passive"))
    )
    (net (code "143") (name "Net-(D1-K)") (class "Default")
      (node (ref "D1") (pin "2") (pinfunction "K_2") (pintype "passive"))
      (node (ref "L1") (pin "1") (pinfunction "1_1") (pintype "passive"))
      (node (ref "U3") (pin "7") (pinfunction "OUT_7") (pintype "open_emitter"))
    )
    (net (code "144") (name "Net-(D20-Pad1)") (class "Default")
      (node (ref "D20") (pin "1") (pinfunction "1_1") (pintype "passive"))
      (node (ref "R26") (pin "3") (pinfunction "3_3") (pintype "passive"))
    )
    (net (code "145") (name "Net-(D20-Pad2)") (class "Default")
      (node (ref "D20") (pin "2") (pinfunction "2_2") (pintype "passive"))
      (node (ref "R26") (pin "2") (pinfunction "2_2") (pintype "passive"))
    )
    (net (code "146") (name "Net-(D21-Pad1)") (class "Default")
      (node (ref "D21") (pin "1") (pinfunction "1_1") (pintype "passive"))
      (node (ref "R26") (pin "4") (pinfunction "4_4") (pintype "passive"))
    )
    (net (code "147") (name "Net-(D21-Pad2)") (class "Default")
      (node (ref "D21") (pin "2") (pinfunction "2_2") (pintype "passive"))
      (node (ref "R26") (pin "1") (pinfunction "1_1") (pintype "passive"))
    )
    (net (code "148") (name "Net-(D22-Pad1)") (class "Default")
      (node (ref "D22") (pin "1") (pinfunction "1_1") (pintype "passive"))
      (node (ref "R27") (pin "1") (pinfunction "1_1") (pintype "passive"))
    )
    (net (code "149") (name "Net-(JP1-Pad1)") (class "Default")
      (node (ref "JP1") (pin "1") (pinfunction "1_1") (pintype "passive"))
      (node (ref "R5") (pin "2") (pinfunction "2_2") (pintype "passive"))
      (node (ref "R6") (pin "2") (pinfunction "2_2") (pintype "passive"))
    )
    (net (code "150") (name "Net-(JP2-Pad2)") (class "Default")
      (node (ref "JP2") (pin "2") (pinfunction "2_2") (pintype "passive"))
      (node (ref "R4") (pin "2") (pinfunction "2_2") (pintype "passive"))
      (node (ref "R5") (pin "1") (pinfunction "1_1") (pintype "passive"))
    )
    (net (code "151") (name "Net-(Q1A-S1)") (class "Default")
      (node (ref "Q1") (pin "1") (pinfunction "S1_1") (pintype "passive"))
      (node (ref "R25") (pin "2") (pinfunction "2_2") (pintype "passive"))
    )
    (net (code "152") (name "Net-(Q1B-S2)") (class "Default")
      (node (ref "Q1") (pin "4") (pinfunction "S2_4") (pintype "passive"))
      (node (ref "R24") (pin "1") (pinfunction "1_1") (pintype "passive"))
    )
    (net (code "153") (name "Net-(Q2-C)") (class "Default")
      (node (ref "Q2") (pin "3") (pinfunction "C_3") (pintype "passive"))
      (node (ref "R19") (pin "2") (pinfunction "2_2") (pintype "passive"))
    )
    (net (code "154") (name "Net-(Q3-C)") (class "Default")
      (node (ref "Q3") (pin "3") (pinfunction "C_3") (pintype "passive"))
      (node (ref "R20") (pin "2") (pinfunction "2_2") (pintype "passive"))
    )
    (net (code "155") (name "Net-(Q4-B)") (class "Default")
      (node (ref "Q4") (pin "1") (pinfunction "B_1") (pintype "passive"))
      (node (ref "Q5") (pin "3") (pinfunction "E_3") (pintype "passive"))
      (node (ref "R23") (pin "2") (pinfunction "2_2") (pintype "passive"))
    )
    (net (code "156") (name "Net-(Q4-C)") (class "Default")
      (node (ref "Q4") (pin "3") (pinfunction "C_3") (pintype "passive"))
      (node (ref "Q5") (pin "1") (pinfunction "B_1") (pintype "passive"))
      (node (ref "R22") (pin "1") (pinfunction "1_1") (pintype "passive"))
    )
    (net (code "157") (name "Net-(Q4-E)") (class "Default")
      (node (ref "CON1") (pin "12B") (pinfunction "12B_12B") (pintype "passive"))
      (node (ref "Q4") (pin "2") (pinfunction "E_2") (pintype "passive"))
      (node (ref "R23") (pin "1") (pinfunction "1_1") (pintype "passive"))
      (node (ref "R32") (pin "2") (pinfunction "2_2") (pintype "passive"))
    )
    (net (code "158") (name "Net-(Q6-C)") (class "Default")
      (node (ref "Q6") (pin "3") (pinfunction "C_3") (pintype "passive"))
      (node (ref "R26") (pin "7") (pinfunction "7_7") (pintype "passive"))
    )
    (net (code "159") (name "Net-(Q7-C)") (class "Default")
      (node (ref "Q7") (pin "3") (pinfunction "C_3") (pintype "passive"))
      (node (ref "R26") (pin "6") (pinfunction "6_6") (pintype "passive"))
    )
    (net (code "160") (name "Net-(Q8-C)") (class "Default")
      (node (ref "Q8") (pin "3") (pinfunction "C_3") (pintype "passive"))
      (node (ref "R26") (pin "8") (pinfunction "6_8") (pintype "passive"))
    )
    (net (code "161") (name "Net-(Q9-C)") (class "Default")
      (node (ref "Q9") (pin "3") (pinfunction "C_3") (pintype "passive"))
      (node (ref "R26") (pin "5") (pinfunction "5_5") (pintype "passive"))
    )
    (net (code "162") (name "Net-(Q10-C)") (class "Default")
      (node (ref "Q10") (pin "3") (pinfunction "C_3") (pintype "passive"))
      (node (ref "R27") (pin "2") (pinfunction "2_2") (pintype "passive"))
    )
    (net (code "163") (name "Net-(Q11-D)") (class "Default")
      (node (ref "Q11") (pin "3") (pinfunction "D_3") (pintype "passive"))
      (node (ref "Q12") (pin "1") (pinfunction "B_1") (pintype "passive"))
      (node (ref "R29") (pin "2") (pinfunction "2_2") (pintype "passive"))
      (node (ref "R30") (pin "2") (pinfunction "2_2") (pintype "passive"))
    )
    (net (code "164") (name "Net-(Q12-C)") (class "Default")
      (node (ref "Q12") (pin "3") (pinfunction "C_3") (pintype "passive"))
      (node (ref "R31") (pin "2") (pinfunction "2_2") (pintype "passive"))
    )
    (net (code "165") (name "Net-(U1-AREF)") (class "Default")
      (node (ref "C17") (pin "2") (pinfunction "2_2") (pintype "passive"))
      (node (ref "U1") (pin "98") (pinfunction "AREF_98") (pintype "passive"))
    )
    (net (code "166") (name "Net-(U1-AVCC)") (class "Default")
      (node (ref "C19") (pin "2") (pinfunction "2_2") (pintype "passive"))
      (node (ref "L2") (pin "2") (pinfunction "2_2") (pintype "passive"))
      (node (ref "U1") (pin "100") (pinfunction "AVCC_100") (pintype "power_in"))
    )
    (net (code "167") (name "Net-(U1-XTAL1)") (class "Default")
      (node (ref "C10") (pin "1") (pinfunction "1_1") (pintype "passive"))
      (node (ref "U1") (pin "34") (pinfunction "XTAL1_34") (pintype "passive"))
      (node (ref "Y1") (pin "1") (pinfunction "OSC1_1") (pintype "passive"))
    )
    (net (code "168") (name "Net-(U1-XTAL2)") (class "Default")
      (node (ref "C11") (pin "1") (pinfunction "1_1") (pintype "passive"))
      (node (ref "U1") (pin "33") (pinfunction "XTAL2_33") (pintype "passive"))
      (node (ref "Y1") (pin "2") (pinfunction "OSC2_2") (pintype "passive"))
    )
    (net (code "169") (name "Net-(U3-FB)") (class "Default")
      (node (ref "C3") (pin "2") (pinfunction "2_2") (pintype "passive"))
      (node (ref "C4") (pin "1") (pinfunction "1_1") (pintype "passive"))
      (node (ref "F1") (pin "1") (pinfunction "1_1") (pintype "passive"))
      (node (ref "L1") (pin "2") (pinfunction "2_2") (pintype "passive"))
      (node (ref "U3") (pin "1") (pinfunction "FB_1") (pintype "input"))
    )
    (net (code "170") (name "Net-(U4-C1+)") (class "Default")
      (node (ref "C13") (pin "1") (pinfunction "1_1") (pintype "passive"))
      (node (ref "U4") (pin "1") (pinfunction "C1+_1") (pintype "passive"))
    )
    (net (code "171") (name "Net-(U4-C1-)") (class "Default")
      (node (ref "C13") (pin "2") (pinfunction "2_2") (pintype "passive"))
      (node (ref "U4") (pin "3") (pinfunction "C1-_3") (pintype "passive"))
    )
    (net (code "172") (name "Net-(U4-C2+)") (class "Default")
      (node (ref "C12") (pin "2") (pinfunction "2_2") (pintype "passive"))
      (node (ref "U4") (pin "4") (pinfunction "C2+_4") (pintype "passive"))
    )
    (net (code "173") (name "Net-(U4-C2-)") (class "Default")
      (node (ref "C12") (pin "1") (pinfunction "1_1") (pintype "passive"))
      (node (ref "U4") (pin "5") (pinfunction "C2-_5") (pintype "passive"))
    )
    (net (code "174") (name "Net-(U4-V+)") (class "Default")
      (node (ref "C14") (pin "2") (pinfunction "2_2") (pintype "passive"))
      (node (ref "U4") (pin "2") (pinfunction "V+_2") (pintype "power_in"))
    )
    (net (code "175") (name "Net-(U4-V-)") (class "Default")
      (node (ref "C16") (pin "2") (pinfunction "2_2") (pintype "passive"))
      (node (ref "U4") (pin "6") (pinfunction "V-_6") (pintype "power_in"))
    )
    (net (code "176") (name "Net-(U7-~{Y}1)") (class "Default")
      (node (ref "R33") (pin "1") (pinfunction "1_1") (pintype "passive"))
      (node (ref "U7") (pin "18") (pinfunction "~{Y}1_18") (pintype "tri_state"))
    )
    (net (code "177") (name "Net-(U7-~{Y}2)") (class "Default")
      (node (ref "R34") (pin "4") (pinfunction "4_4") (pintype "passive"))
      (node (ref "U7") (pin "17") (pinfunction "~{Y}2_17") (pintype "tri_state"))
    )
    (net (code "178") (name "Net-(U7-~{Y}3)") (class "Default")
      (node (ref "R33") (pin "2") (pinfunction "2_2") (pintype "passive"))
      (node (ref "U7") (pin "16") (pinfunction "~{Y}3_16") (pintype "tri_state"))
    )
    (net (code "179") (name "Net-(U7-~{Y}4)") (class "Default")
      (node (ref "R34") (pin "3") (pinfunction "3_3") (pintype "passive"))
      (node (ref "U7") (pin "15") (pinfunction "~{Y}4_15") (pintype "tri_state"))
    )
    (net (code "180") (name "Net-(U7-~{Y}5)") (class "Default")
      (node (ref "R33") (pin "3") (pinfunction "3_3") (pintype "passive"))
      (node (ref "U7") (pin "14") (pinfunction "~{Y}5_14") (pintype "tri_state"))
    )
    (net (code "181") (name "Net-(U7-~{Y}6)") (class "Default")
      (node (ref "R34") (pin "2") (pinfunction "2_2") (pintype "passive"))
      (node (ref "U7") (pin "13") (pinfunction "~{Y}6_13") (pintype "tri_state"))
    )
    (net (code "182") (name "Net-(U7-~{Y}7)") (class "Default")
      (node (ref "R33") (pin "4") (pinfunction "4_4") (pintype "passive"))
      (node (ref "U7") (pin "12") (pinfunction "~{Y}7_12") (pintype "tri_state"))
    )
    (net (code "183") (name "Net-(U7-~{Y}8)") (class "Default")
      (node (ref "R34") (pin "1") (pinfunction "1_1") (pintype "passive"))
      (node (ref "U7") (pin "11") (pinfunction "~{Y}8_11") (pintype "tri_state"))
    )
    (net (code "184") (name "VCC") (class "Default")
      (node (ref "C14") (pin "1") (pinfunction "1_1") (pintype "passive"))
      (node (ref "C15") (pin "1") (pinfunction "1_1") (pintype "passive"))
      (node (ref "C18") (pin "2") (pinfunction "2_2") (pintype "passive"))
      (node (ref "C20") (pin "2") (pinfunction "2_2") (pintype "passive"))
      (node (ref "C21") (pin "2") (pinfunction "2_2") (pintype "passive"))
      (node (ref "C22") (pin "2") (pinfunction "2_2") (pintype "passive"))
      (node (ref "C5") (pin "2") (pinfunction "2_2") (pintype "passive"))
      (node (ref "C6") (pin "2") (pinfunction "2_2") (pintype "passive"))
      (node (ref "C7") (pin "2") (pinfunction "2_2") (pintype "passive"))
      (node (ref "C8") (pin "2") (pinfunction "2_2") (pintype "passive"))
      (node (ref "CON1") (pin "12") (pinfunction "12_12") (pintype "passive"))
      (node (ref "CON3") (pin "1") (pinfunction "1_1") (pintype "passive"))
      (node (ref "D19") (pin "1") (pinfunction "VCC_1") (pintype "power_in"))
      (node (ref "D19") (pin "8") (pinfunction "VCC_8") (pintype "power_in"))
      (node (ref "F1") (pin "2") (pinfunction "2_2") (pintype "passive"))
      (node (ref "JP6") (pin "4") (pinfunction "4_4") (pintype "passive"))
      (node (ref "L2") (pin "1") (pinfunction "1_1") (pintype "passive"))
      (node (ref "Q10") (pin "2") (pinfunction "E_2") (pintype "passive"))
      (node (ref "Q11") (pin "2") (pinfunction "S_2") (pintype "passive"))
      (node (ref "Q12") (pin "2") (pinfunction "E_2") (pintype "passive"))
      (node (ref "Q3") (pin "2") (pinfunction "E_2") (pintype "passive"))
      (node (ref "Q6") (pin "2") (pinfunction "E_2") (pintype "passive"))
      (node (ref "Q7") (pin "2") (pinfunction "E_2") (pintype "passive"))
      (node (ref "Q8") (pin "2") (pinfunction "E_2") (pintype "passive"))
      (node (ref "Q9") (pin "2") (pinfunction "E_2") (pintype "passive"))
      (node (ref "R1") (pin "2") (pinfunction "2_2") (pintype "passive"))
      (node (ref "R21") (pin "2") (pinfunction "2_2") (pintype "passive"))
      (node (ref "R24") (pin "2") (pinfunction "2_2") (pintype "passive"))
      (node (ref "R28") (pin "2") (pinfunction "2_2") (pintype "passive"))
      (node (ref "R3") (pin "2") (pinfunction "2_2") (pintype "passive"))
      (node (ref "R6") (pin "1") (pinfunction "1_1") (pintype "passive"))
      (node (ref "R67") (pin "2") (pinfunction "2_2") (pintype "passive"))
      (node (ref "R68") (pin "2") (pinfunction "2_2") (pintype "passive"))
      (node (ref "U1") (pin "10") (pinfunction "VCC_10") (pintype "passive"))
      (node (ref "U1") (pin "31") (pinfunction "VCC_31") (pintype "passive"))
      (node (ref "U1") (pin "61") (pinfunction "VCC_61") (pintype "power_in"))
      (node (ref "U1") (pin "80") (pinfunction "VCC_80") (pintype "passive"))
      (node (ref "U2") (pin "8") (pinfunction "VCC_8") (pintype "power_in"))
      (node (ref "U4") (pin "16") (pinfunction "VCC_16") (pintype "power_in"))
      (node (ref "U5") (pin "5") (pinfunction "VCC_5") (pintype "power_in"))
      (node (ref "U6") (pin "3") (pinfunction "VCC_3") (pintype "power_in"))
      (node (ref "U7") (pin "20") (pinfunction "VCC_20") (pintype "power_in"))
    )
    (net (code "185") (name "unconnected-(U4-R1OUT-Pad12)") (class "Default")
      (node (ref "U4") (pin "12") (pinfunction "R1OUT_12") (pintype "output"))
    )
    (net (code "186") (name "unconnected-(U4-T1OUT-Pad14)") (class "Default")
      (node (ref "U4") (pin "14") (pinfunction "T1OUT_14") (pintype "output"))
    )
  )
)
